# UPCNSL-ABS-FLS-ARD.net
KiCad netlist of a schematic drawn in Altium Designer
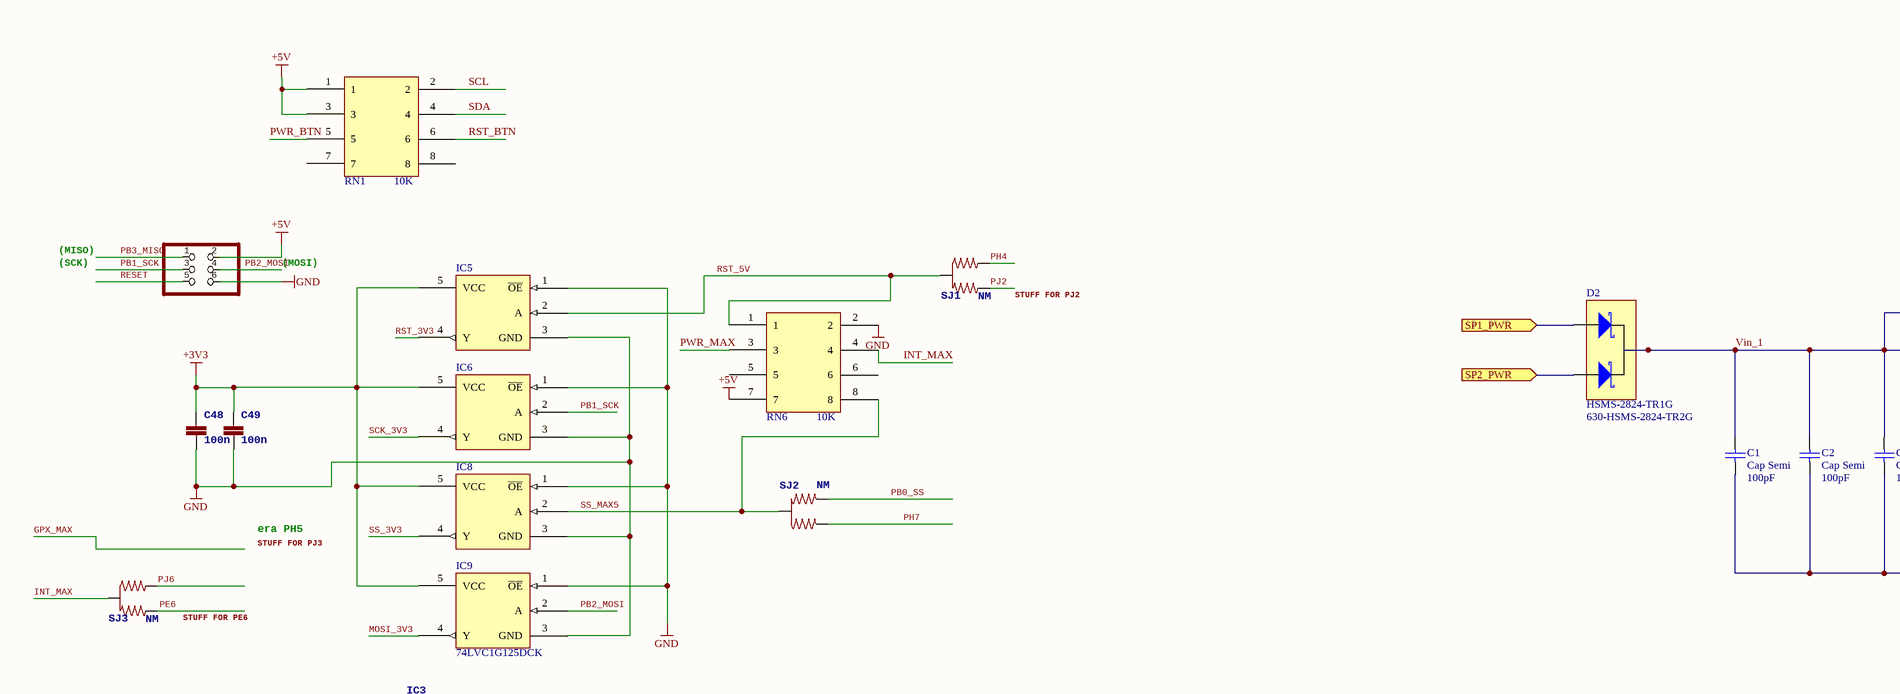
[diagram p0: UPCNSL-ABS-FLS-ARD.SchDoc, top left]
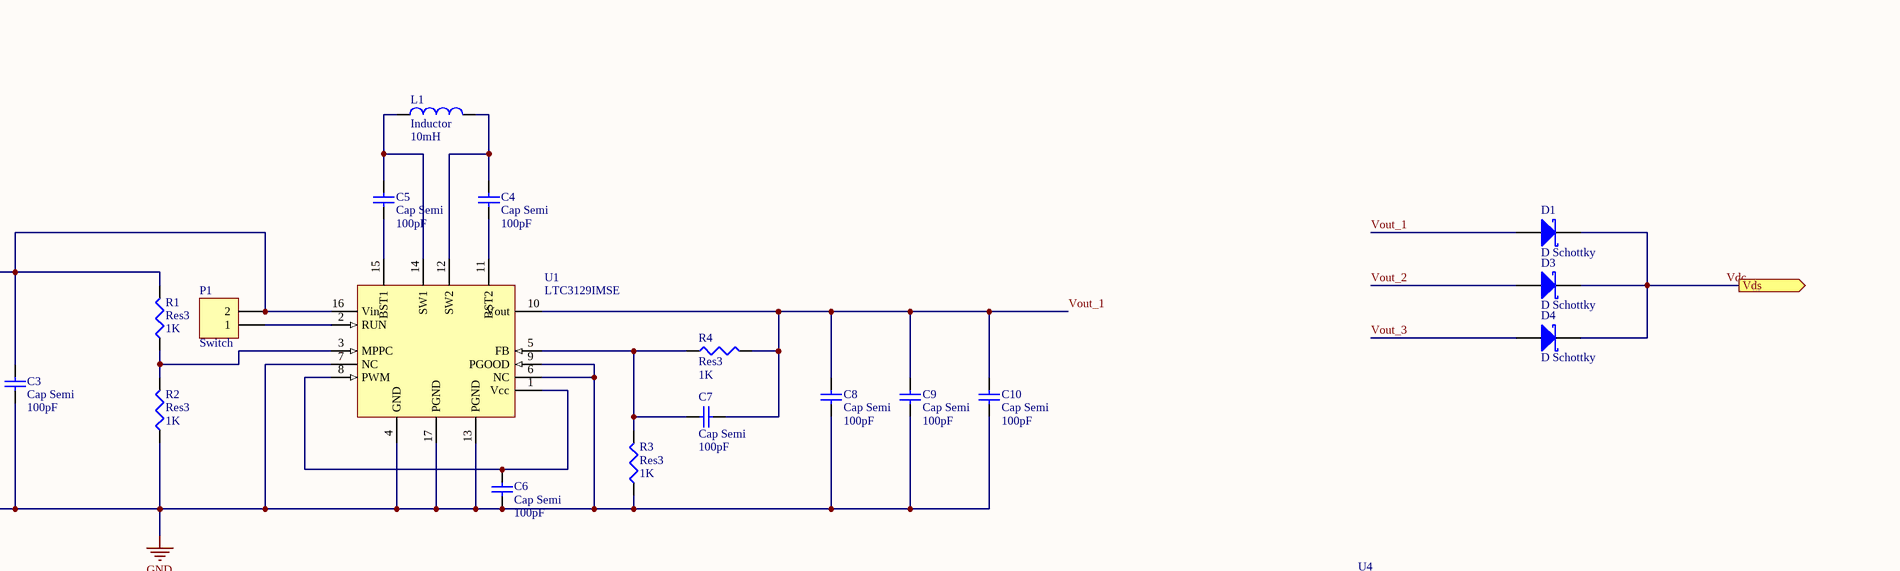
[diagram p1: UPCNSL-ABS-FLS-ARD.SchDoc, top right]
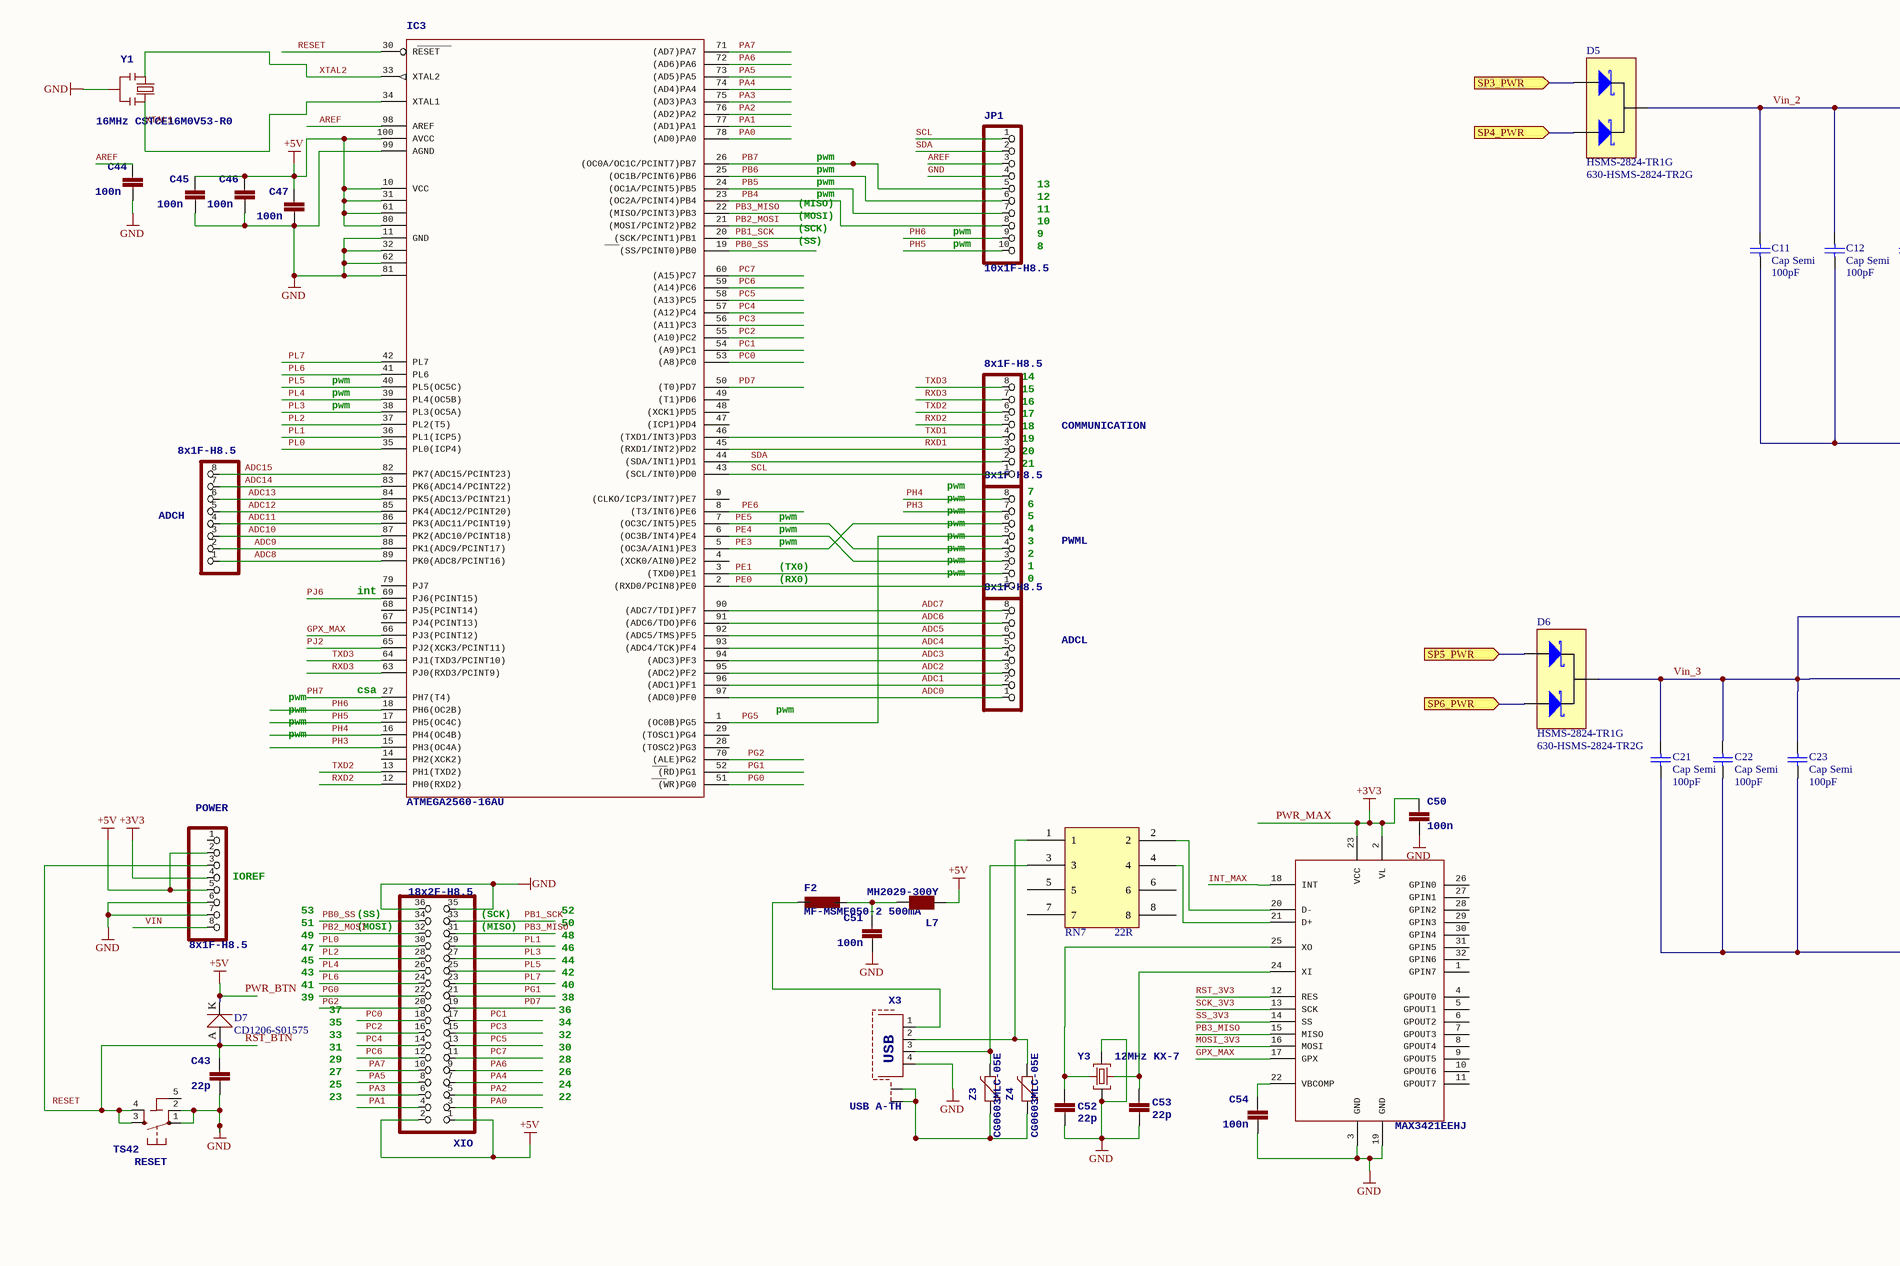
[diagram p2: UPCNSL-ABS-FLS-ARD.SchDoc, bottom left]
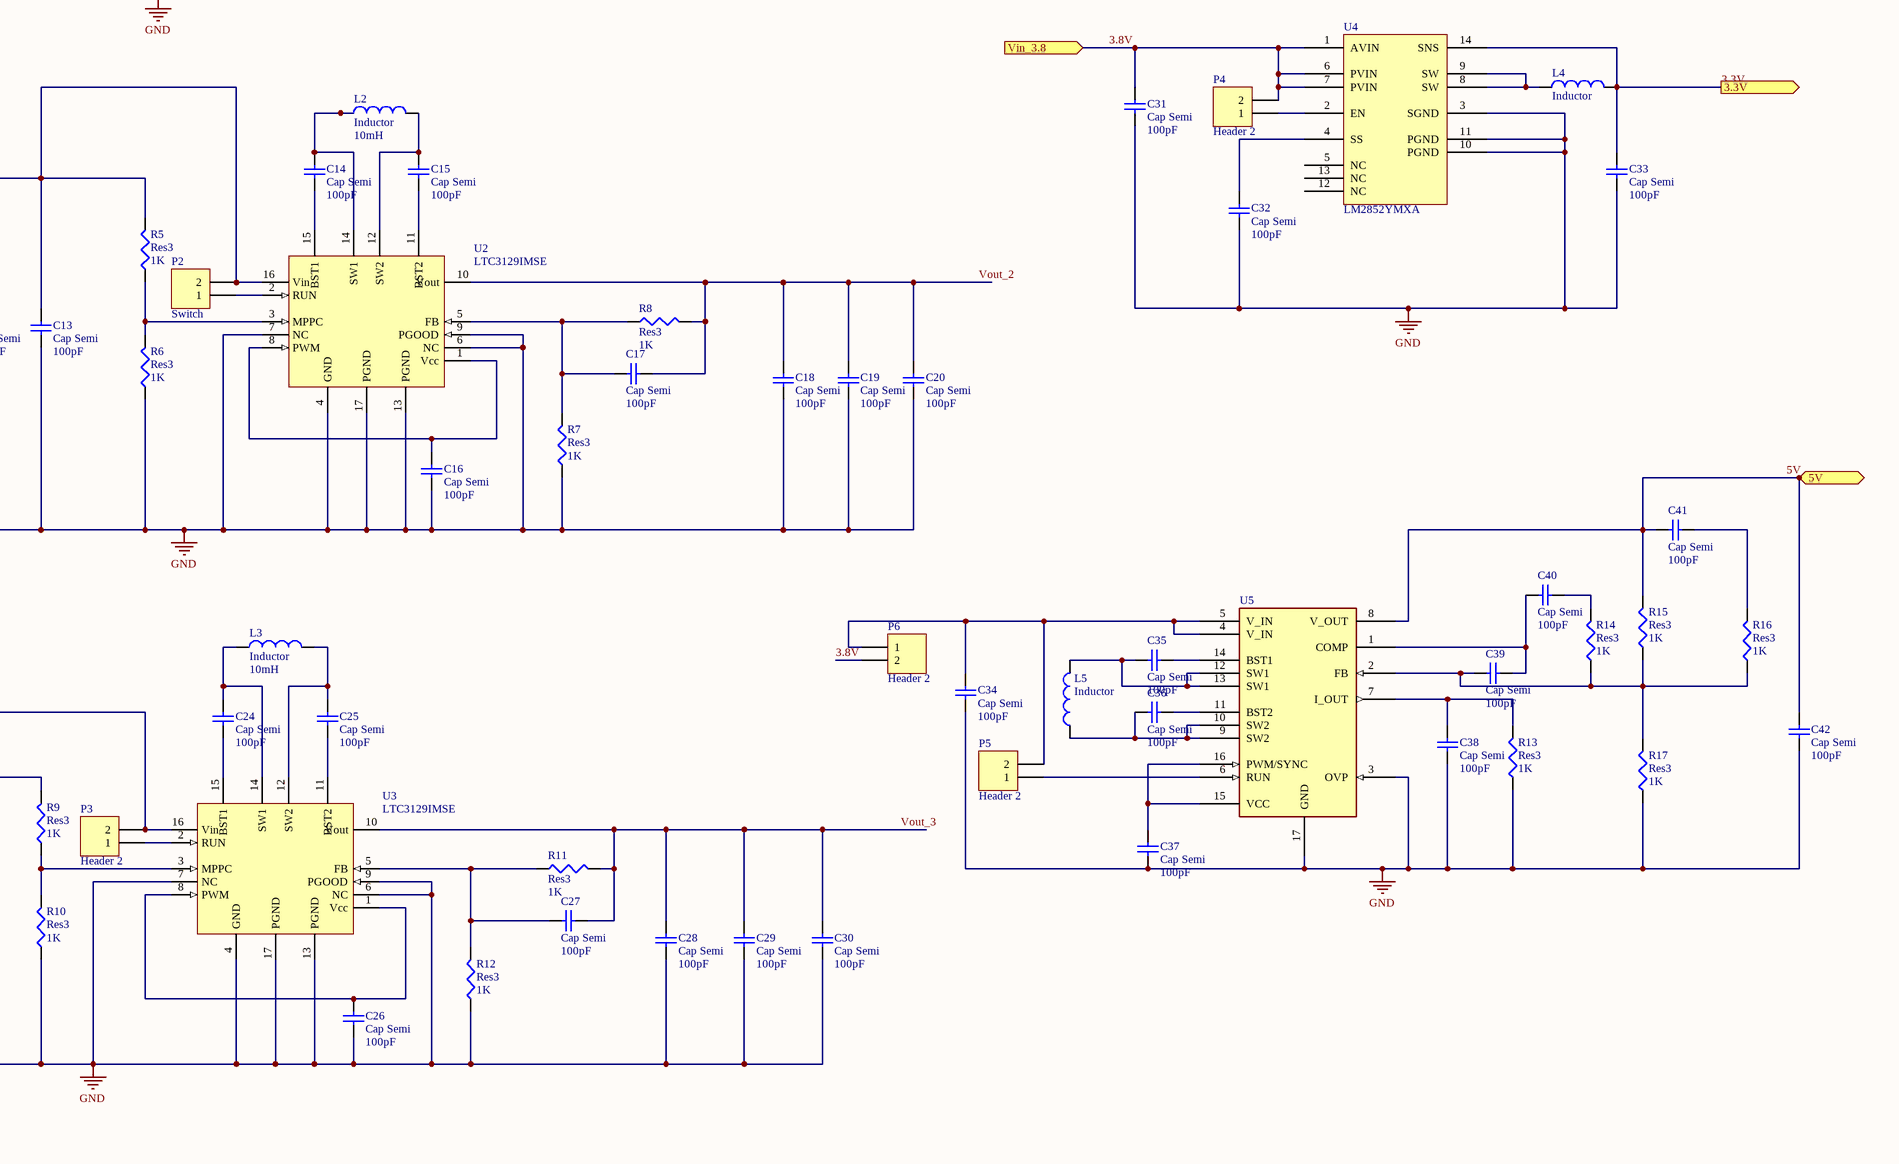
[diagram p3: UPCNSL-ABS-FLS-ARD.SchDoc, bottom right]

(export (version "E")
  (design (tool "Eeschema 10.0.6"))
  (components
    (comp (ref "ADCH")
      (value "8x1F-H8.5")
      (footprint "ADCH")
      (description "<b>PIN HEADER</b>")
      (libsource (lib "SmartPrj") (part "PINHD-1X8"))
    )
    (comp (ref "ADCL")
      (value "8x1F-H8.5")
      (footprint "ADCL")
      (description "<b>PIN HEADER</b>")
      (libsource (lib "SmartPrj") (part "PINHD-1X8"))
    )
    (comp (ref "C1")
      (value "Cap Semi")
      (footprint "1608[0603]")
      (description "Capacitor (Semiconductor SIM Model)")
      (fields (field (name "ALTIUM_VALUE") "100pF") (field (name "PUBLISHER") "Altium Limited"))
      (libsource (lib "Miscellaneous Devices") (part "Cap Semi"))
    )
    (comp (ref "C2")
      (value "Cap Semi")
      (footprint "1608[0603]")
      (description "Capacitor (Semiconductor SIM Model)")
      (fields (field (name "ALTIUM_VALUE") "100pF") (field (name "PUBLISHER") "Altium Limited"))
      (libsource (lib "Miscellaneous Devices") (part "Cap Semi"))
    )
    (comp (ref "C3")
      (value "Cap Semi")
      (footprint "1608[0603]")
      (description "Capacitor (Semiconductor SIM Model)")
      (fields (field (name "ALTIUM_VALUE") "100pF") (field (name "PUBLISHER") "Altium Limited"))
      (libsource (lib "Miscellaneous Devices") (part "Cap Semi"))
    )
    (comp (ref "C4")
      (value "Cap Semi")
      (footprint "1608[0603]")
      (description "Capacitor (Semiconductor SIM Model)")
      (fields (field (name "ALTIUM_VALUE") "100pF") (field (name "PUBLISHER") "Altium Limited"))
      (libsource (lib "Miscellaneous Devices") (part "Cap Semi"))
    )
    (comp (ref "C5")
      (value "Cap Semi")
      (footprint "1608[0603]")
      (description "Capacitor (Semiconductor SIM Model)")
      (fields (field (name "ALTIUM_VALUE") "100pF") (field (name "PUBLISHER") "Altium Limited"))
      (libsource (lib "Miscellaneous Devices") (part "Cap Semi"))
    )
    (comp (ref "C6")
      (value "Cap Semi")
      (footprint "1608[0603]")
      (description "Capacitor (Semiconductor SIM Model)")
      (fields (field (name "ALTIUM_VALUE") "100pF") (field (name "PUBLISHER") "Altium Limited"))
      (libsource (lib "Miscellaneous Devices") (part "Cap Semi"))
    )
    (comp (ref "C7")
      (value "Cap Semi")
      (footprint "1608[0603]")
      (description "Capacitor (Semiconductor SIM Model)")
      (fields (field (name "ALTIUM_VALUE") "100pF") (field (name "PUBLISHER") "Altium Limited"))
      (libsource (lib "Miscellaneous Devices") (part "Cap Semi"))
    )
    (comp (ref "C8")
      (value "Cap Semi")
      (footprint "1608[0603]")
      (description "Capacitor (Semiconductor SIM Model)")
      (fields (field (name "ALTIUM_VALUE") "100pF") (field (name "PUBLISHER") "Altium Limited"))
      (libsource (lib "Miscellaneous Devices") (part "Cap Semi"))
    )
    (comp (ref "C9")
      (value "Cap Semi")
      (footprint "1608[0603]")
      (description "Capacitor (Semiconductor SIM Model)")
      (fields (field (name "ALTIUM_VALUE") "100pF") (field (name "PUBLISHER") "Altium Limited"))
      (libsource (lib "Miscellaneous Devices") (part "Cap Semi"))
    )
    (comp (ref "C10")
      (value "Cap Semi")
      (footprint "1608[0603]")
      (description "Capacitor (Semiconductor SIM Model)")
      (fields (field (name "ALTIUM_VALUE") "100pF") (field (name "PUBLISHER") "Altium Limited"))
      (libsource (lib "Miscellaneous Devices") (part "Cap Semi"))
    )
    (comp (ref "C11")
      (value "Cap Semi")
      (footprint "1608[0603]")
      (description "Capacitor (Semiconductor SIM Model)")
      (fields (field (name "ALTIUM_VALUE") "100pF") (field (name "PUBLISHER") "Altium Limited"))
      (libsource (lib "Miscellaneous Devices") (part "Cap Semi"))
    )
    (comp (ref "C12")
      (value "Cap Semi")
      (footprint "1608[0603]")
      (description "Capacitor (Semiconductor SIM Model)")
      (fields (field (name "ALTIUM_VALUE") "100pF") (field (name "PUBLISHER") "Altium Limited"))
      (libsource (lib "Miscellaneous Devices") (part "Cap Semi"))
    )
    (comp (ref "C13")
      (value "Cap Semi")
      (footprint "1608[0603]")
      (description "Capacitor (Semiconductor SIM Model)")
      (fields (field (name "ALTIUM_VALUE") "100pF") (field (name "PUBLISHER") "Altium Limited"))
      (libsource (lib "Miscellaneous Devices") (part "Cap Semi"))
    )
    (comp (ref "C14")
      (value "Cap Semi")
      (footprint "1608[0603]")
      (description "Capacitor (Semiconductor SIM Model)")
      (fields (field (name "ALTIUM_VALUE") "100pF") (field (name "PUBLISHER") "Altium Limited"))
      (libsource (lib "Miscellaneous Devices") (part "Cap Semi"))
    )
    (comp (ref "C15")
      (value "Cap Semi")
      (footprint "1608[0603]")
      (description "Capacitor (Semiconductor SIM Model)")
      (fields (field (name "ALTIUM_VALUE") "100pF") (field (name "PUBLISHER") "Altium Limited"))
      (libsource (lib "Miscellaneous Devices") (part "Cap Semi"))
    )
    (comp (ref "C16")
      (value "Cap Semi")
      (footprint "1608[0603]")
      (description "Capacitor (Semiconductor SIM Model)")
      (fields (field (name "ALTIUM_VALUE") "100pF") (field (name "PUBLISHER") "Altium Limited"))
      (libsource (lib "Miscellaneous Devices") (part "Cap Semi"))
    )
    (comp (ref "C17")
      (value "Cap Semi")
      (footprint "1608[0603]")
      (description "Capacitor (Semiconductor SIM Model)")
      (fields (field (name "ALTIUM_VALUE") "100pF") (field (name "PUBLISHER") "Altium Limited"))
      (libsource (lib "Miscellaneous Devices") (part "Cap Semi"))
    )
    (comp (ref "C18")
      (value "Cap Semi")
      (footprint "1608[0603]")
      (description "Capacitor (Semiconductor SIM Model)")
      (fields (field (name "ALTIUM_VALUE") "100pF") (field (name "PUBLISHER") "Altium Limited"))
      (libsource (lib "Miscellaneous Devices") (part "Cap Semi"))
    )
    (comp (ref "C19")
      (value "Cap Semi")
      (footprint "1608[0603]")
      (description "Capacitor (Semiconductor SIM Model)")
      (fields (field (name "ALTIUM_VALUE") "100pF") (field (name "PUBLISHER") "Altium Limited"))
      (libsource (lib "Miscellaneous Devices") (part "Cap Semi"))
    )
    (comp (ref "C20")
      (value "Cap Semi")
      (footprint "1608[0603]")
      (description "Capacitor (Semiconductor SIM Model)")
      (fields (field (name "ALTIUM_VALUE") "100pF") (field (name "PUBLISHER") "Altium Limited"))
      (libsource (lib "Miscellaneous Devices") (part "Cap Semi"))
    )
    (comp (ref "C21")
      (value "Cap Semi")
      (footprint "1608[0603]")
      (description "Capacitor (Semiconductor SIM Model)")
      (fields (field (name "ALTIUM_VALUE") "100pF") (field (name "PUBLISHER") "Altium Limited"))
      (libsource (lib "Miscellaneous Devices") (part "Cap Semi"))
    )
    (comp (ref "C22")
      (value "Cap Semi")
      (footprint "1608[0603]")
      (description "Capacitor (Semiconductor SIM Model)")
      (fields (field (name "ALTIUM_VALUE") "100pF") (field (name "PUBLISHER") "Altium Limited"))
      (libsource (lib "Miscellaneous Devices") (part "Cap Semi"))
    )
    (comp (ref "C23")
      (value "Cap Semi")
      (footprint "1608[0603]")
      (description "Capacitor (Semiconductor SIM Model)")
      (fields (field (name "ALTIUM_VALUE") "100pF") (field (name "PUBLISHER") "Altium Limited"))
      (libsource (lib "Miscellaneous Devices") (part "Cap Semi"))
    )
    (comp (ref "C24")
      (value "Cap Semi")
      (footprint "1608[0603]")
      (description "Capacitor (Semiconductor SIM Model)")
      (fields (field (name "ALTIUM_VALUE") "100pF") (field (name "PUBLISHER") "Altium Limited"))
      (libsource (lib "Miscellaneous Devices") (part "Cap Semi"))
    )
    (comp (ref "C25")
      (value "Cap Semi")
      (footprint "1608[0603]")
      (description "Capacitor (Semiconductor SIM Model)")
      (fields (field (name "ALTIUM_VALUE") "100pF") (field (name "PUBLISHER") "Altium Limited"))
      (libsource (lib "Miscellaneous Devices") (part "Cap Semi"))
    )
    (comp (ref "C26")
      (value "Cap Semi")
      (footprint "1608[0603]")
      (description "Capacitor (Semiconductor SIM Model)")
      (fields (field (name "ALTIUM_VALUE") "100pF") (field (name "PUBLISHER") "Altium Limited"))
      (libsource (lib "Miscellaneous Devices") (part "Cap Semi"))
    )
    (comp (ref "C27")
      (value "Cap Semi")
      (footprint "1608[0603]")
      (description "Capacitor (Semiconductor SIM Model)")
      (fields (field (name "ALTIUM_VALUE") "100pF") (field (name "PUBLISHER") "Altium Limited"))
      (libsource (lib "Miscellaneous Devices") (part "Cap Semi"))
    )
    (comp (ref "C28")
      (value "Cap Semi")
      (footprint "1608[0603]")
      (description "Capacitor (Semiconductor SIM Model)")
      (fields (field (name "ALTIUM_VALUE") "100pF") (field (name "PUBLISHER") "Altium Limited"))
      (libsource (lib "Miscellaneous Devices") (part "Cap Semi"))
    )
    (comp (ref "C29")
      (value "Cap Semi")
      (footprint "1608[0603]")
      (description "Capacitor (Semiconductor SIM Model)")
      (fields (field (name "ALTIUM_VALUE") "100pF") (field (name "PUBLISHER") "Altium Limited"))
      (libsource (lib "Miscellaneous Devices") (part "Cap Semi"))
    )
    (comp (ref "C30")
      (value "Cap Semi")
      (footprint "1608[0603]")
      (description "Capacitor (Semiconductor SIM Model)")
      (fields (field (name "ALTIUM_VALUE") "100pF") (field (name "PUBLISHER") "Altium Limited"))
      (libsource (lib "Miscellaneous Devices") (part "Cap Semi"))
    )
    (comp (ref "C31")
      (value "Cap Semi")
      (footprint "1608[0603]")
      (description "Capacitor (Semiconductor SIM Model)")
      (fields (field (name "ALTIUM_VALUE") "100pF") (field (name "PUBLISHER") "Altium Limited"))
      (libsource (lib "Miscellaneous Devices") (part "Cap Semi"))
    )
    (comp (ref "C32")
      (value "Cap Semi")
      (footprint "1608[0603]")
      (description "Capacitor (Semiconductor SIM Model)")
      (fields (field (name "ALTIUM_VALUE") "100pF") (field (name "PUBLISHER") "Altium Limited"))
      (libsource (lib "Miscellaneous Devices") (part "Cap Semi"))
    )
    (comp (ref "C33")
      (value "Cap Semi")
      (footprint "1608[0603]")
      (description "Capacitor (Semiconductor SIM Model)")
      (fields (field (name "ALTIUM_VALUE") "100pF") (field (name "PUBLISHER") "Altium Limited"))
      (libsource (lib "Miscellaneous Devices") (part "Cap Semi"))
    )
    (comp (ref "C34")
      (value "Cap Semi")
      (footprint "1608[0603]")
      (description "Capacitor (Semiconductor SIM Model)")
      (fields (field (name "ALTIUM_VALUE") "100pF") (field (name "PUBLISHER") "Altium Limited"))
      (libsource (lib "Miscellaneous Devices") (part "Cap Semi"))
    )
    (comp (ref "C35")
      (value "Cap Semi")
      (footprint "1608[0603]")
      (description "Capacitor (Semiconductor SIM Model)")
      (fields (field (name "ALTIUM_VALUE") "100pF") (field (name "PUBLISHER") "Altium Limited"))
      (libsource (lib "Miscellaneous Devices") (part "Cap Semi"))
    )
    (comp (ref "C36")
      (value "Cap Semi")
      (footprint "1608[0603]")
      (description "Capacitor (Semiconductor SIM Model)")
      (fields (field (name "ALTIUM_VALUE") "100pF") (field (name "PUBLISHER") "Altium Limited"))
      (libsource (lib "Miscellaneous Devices") (part "Cap Semi"))
    )
    (comp (ref "C37")
      (value "Cap Semi")
      (footprint "1608[0603]")
      (description "Capacitor (Semiconductor SIM Model)")
      (fields (field (name "ALTIUM_VALUE") "100pF") (field (name "PUBLISHER") "Altium Limited"))
      (libsource (lib "Miscellaneous Devices") (part "Cap Semi"))
    )
    (comp (ref "C38")
      (value "Cap Semi")
      (footprint "1608[0603]")
      (description "Capacitor (Semiconductor SIM Model)")
      (fields (field (name "ALTIUM_VALUE") "100pF") (field (name "PUBLISHER") "Altium Limited"))
      (libsource (lib "Miscellaneous Devices") (part "Cap Semi"))
    )
    (comp (ref "C39")
      (value "Cap Semi")
      (footprint "1608[0603]")
      (description "Capacitor (Semiconductor SIM Model)")
      (fields (field (name "ALTIUM_VALUE") "100pF") (field (name "PUBLISHER") "Altium Limited"))
      (libsource (lib "Miscellaneous Devices") (part "Cap Semi"))
    )
    (comp (ref "C40")
      (value "Cap Semi")
      (footprint "1608[0603]")
      (description "Capacitor (Semiconductor SIM Model)")
      (fields (field (name "ALTIUM_VALUE") "100pF") (field (name "PUBLISHER") "Altium Limited"))
      (libsource (lib "Miscellaneous Devices") (part "Cap Semi"))
    )
    (comp (ref "C41")
      (value "Cap Semi")
      (footprint "1608[0603]")
      (description "Capacitor (Semiconductor SIM Model)")
      (fields (field (name "ALTIUM_VALUE") "100pF") (field (name "PUBLISHER") "Altium Limited"))
      (libsource (lib "Miscellaneous Devices") (part "Cap Semi"))
    )
    (comp (ref "C42")
      (value "Cap Semi")
      (footprint "1608[0603]")
      (description "Capacitor (Semiconductor SIM Model)")
      (fields (field (name "ALTIUM_VALUE") "100pF") (field (name "PUBLISHER") "Altium Limited"))
      (libsource (lib "Miscellaneous Devices") (part "Cap Semi"))
    )
    (comp (ref "C43")
      (value "22p")
      (footprint "CAP0603")
      (description "<B>CAPACITOR</B>, European symbol")
      (fields (field (name ">NAME") "C43") (field (name ">VALUE") "22p"))
      (libsource (lib "SmartPrj") (part "C-EU0603-RND"))
    )
    (comp (ref "C44")
      (value "100n")
      (footprint "CAP0603")
      (description "<B>CAPACITOR</B>, European symbol")
      (libsource (lib "SmartPrj") (part "C-EU0603-RND"))
    )
    (comp (ref "C45")
      (value "100n")
      (footprint "CAP0603")
      (description "<B>CAPACITOR</B>, European symbol")
      (libsource (lib "SmartPrj") (part "C-EU0603-RND"))
    )
    (comp (ref "C46")
      (value "100n")
      (footprint "CAP0603")
      (description "<B>CAPACITOR</B>, European symbol")
      (libsource (lib "SmartPrj") (part "C-EU0603-RND"))
    )
    (comp (ref "C47")
      (value "100n")
      (footprint "CAP0603")
      (description "<B>CAPACITOR</B>, European symbol")
      (libsource (lib "SmartPrj") (part "C-EU0603-RND"))
    )
    (comp (ref "C48")
      (value "100n")
      (footprint "CAP0603")
      (description "<B>CAPACITOR</B>, European symbol")
      (fields (field (name ">NAME") "C48") (field (name ">VALUE") "100n"))
      (libsource (lib "") (part "C-EU0603-RND_2"))
    )
    (comp (ref "C49")
      (value "100n")
      (footprint "CAP0603")
      (description "<B>CAPACITOR</B>, European symbol")
      (fields (field (name ">NAME") "C49") (field (name ">VALUE") "100n"))
      (libsource (lib "") (part "C-EU0603-RND_2"))
    )
    (comp (ref "C50")
      (value "100n")
      (footprint "CAP0603")
      (description "<B>CAPACITOR</B>, European symbol")
      (fields (field (name ">NAME") "C50") (field (name ">VALUE") "100n"))
      (libsource (lib "") (part "C-EU0603-RND_2"))
    )
    (comp (ref "C51")
      (value "100n")
      (footprint "CAP0603")
      (description "<B>CAPACITOR</B>, European symbol")
      (fields (field (name ">NAME") "C51") (field (name ">VALUE") "100n"))
      (libsource (lib "SmartPrj") (part "C-EU0603-RND"))
    )
    (comp (ref "C52")
      (value "22p")
      (footprint "CAP0603")
      (description "<B>CAPACITOR</B>, European symbol")
      (libsource (lib "") (part "C-EU0603-RND_1"))
    )
    (comp (ref "C53")
      (value "22p")
      (footprint "CAP0603")
      (description "<B>CAPACITOR</B>, European symbol")
      (libsource (lib "") (part "C-EU0603-RND_1"))
    )
    (comp (ref "C54")
      (value "100n")
      (footprint "CAP0603")
      (description "<B>CAPACITOR</B>, European symbol")
      (fields (field (name ">NAME") "C54") (field (name ">VALUE") "100n"))
      (libsource (lib "SmartPrj") (part "C-EU0603-RND"))
    )
    (comp (ref "COMMUNICATION")
      (value "8x1F-H8.5")
      (footprint "COMMUNICATION")
      (description "<b>PIN HEADER</b>")
      (libsource (lib "SmartPrj") (part "PINHD-1X8"))
    )
    (comp (ref "D1")
      (value "D Schottky")
      (footprint "SMB")
      (description "Schottky Diode")
      (fields (field (name "PUBLISHER") "Altium Limited"))
      (libsource (lib "Miscellaneous Devices") (part "D Schottky"))
    )
    (comp (ref "D2")
      (value "HSMS-2824-TR1G")
      (footprint "SOT23-3")
      (description "DIODE, RF, SCHOTTKY, DUAL, SOT-23")
      (fields (field (name "SUPPLIER PART NUMBER 1") "630-HSMS-2824-TR2G"))
      (libsource (lib "Arduino_Space") (part "HSMS-2824-TR1G"))
    )
    (comp (ref "D3")
      (value "D Schottky")
      (footprint "SMB")
      (description "Schottky Diode")
      (fields (field (name "PUBLISHER") "Altium Limited"))
      (libsource (lib "Miscellaneous Devices") (part "D Schottky"))
    )
    (comp (ref "D4")
      (value "D Schottky")
      (footprint "SMB")
      (description "Schottky Diode")
      (fields (field (name "PUBLISHER") "Altium Limited"))
      (libsource (lib "Miscellaneous Devices") (part "D Schottky"))
    )
    (comp (ref "D5")
      (value "HSMS-2824-TR1G")
      (footprint "SOT23-3")
      (description "DIODE, RF, SCHOTTKY, DUAL, SOT-23")
      (fields (field (name "SUPPLIER PART NUMBER 1") "630-HSMS-2824-TR2G"))
      (libsource (lib "Arduino_Space") (part "HSMS-2824-TR1G"))
    )
    (comp (ref "D6")
      (value "HSMS-2824-TR1G")
      (footprint "SOT23-3")
      (description "DIODE, RF, SCHOTTKY, DUAL, SOT-23")
      (fields (field (name "SUPPLIER PART NUMBER 1") "630-HSMS-2824-TR2G"))
      (libsource (lib "Arduino_Space") (part "HSMS-2824-TR1G"))
    )
    (comp (ref "D7")
      (value "CD1206-S01575")
      (footprint "SMD DIODE")
      (libsource (lib "Arduino_Space") (part "DIODE"))
    )
    (comp (ref "F2")
      (value "MF-MSMF050-2 500mA")
      (footprint "FUSE")
      (description "<B>INDUCTOR</B>, European symbol")
      (fields (field (name ">NAME") "F2") (field (name ">VALUE") "MF-MSMF050-2 500mA"))
      (libsource (lib "rcl") (part "L-EUL1812"))
    )
    (comp (ref "IC3")
      (value "ATMEGA2560-16AU")
      (footprint "TSQFP50P1600X1600X120-100N")
      (libsource (lib "SmartPrj") (part "ATMEGA2560AU"))
    )
    (comp (ref "IC5")
      (value "74LVC1G125DCK")
      (footprint "SOT65P210X110-5N")
      (libsource (lib "Arduino_Space") (part "74LVC1G125DCK"))
    )
    (comp (ref "IC6")
      (value "74LVC1G125DCK")
      (footprint "SOT65P210X110-5N")
      (libsource (lib "Arduino_Space") (part "74LVC1G125DCK"))
    )
    (comp (ref "IC8")
      (value "74LVC1G125DCK")
      (footprint "SOT65P210X110-5N")
      (libsource (lib "Arduino_Space") (part "74LVC1G125DCK"))
    )
    (comp (ref "IC9")
      (value "74LVC1G125DCK")
      (footprint "SOT65P210X110-5N")
      (libsource (lib "Arduino_Space") (part "74LVC1G125DCK"))
    )
    (comp (ref "ICSP")
      (value "3x2M")
      (footprint "Header 3x2")
      (description "<b>PIN HEADER</b>")
      (libsource (lib "SmartPrj") (part "PINHD-2X3"))
    )
    (comp (ref "JP1")
      (value "10x1F-H8.5")
      (footprint "HEADER 1X10")
      (description "<b>PIN HEADER</b>")
      (fields (field (name ">NAME") "JP1") (field (name ">VALUE") "10x1F-H8.5"))
      (libsource (lib "SmartPrj") (part "PINHD-1X10"))
    )
    (comp (ref "L1")
      (value "Inductor")
      (footprint "0603")
      (fields (field (name "ALTIUM_VALUE") "10mH") (field (name "PUBLISHER") "Altium Limited"))
      (libsource (lib "Miscellaneous Devices") (part "Inductor"))
    )
    (comp (ref "L2")
      (value "Inductor")
      (footprint "0603")
      (fields (field (name "ALTIUM_VALUE") "10mH") (field (name "PUBLISHER") "Altium Limited"))
      (libsource (lib "Miscellaneous Devices") (part "Inductor"))
    )
    (comp (ref "L3")
      (value "Inductor")
      (footprint "0603")
      (fields (field (name "ALTIUM_VALUE") "10mH") (field (name "PUBLISHER") "Altium Limited"))
      (libsource (lib "Miscellaneous Devices") (part "Inductor"))
    )
    (comp (ref "L4")
      (value "Inductor")
      (footprint "0402-A")
      (fields (field (name "PUBLISHER") "Altium Limited"))
      (libsource (lib "Miscellaneous Devices") (part "Inductor"))
    )
    (comp (ref "L5")
      (value "Inductor")
      (footprint "0402-A")
      (fields (field (name "PUBLISHER") "Altium Limited"))
      (libsource (lib "Miscellaneous Devices") (part "Inductor"))
    )
    (comp (ref "L7")
      (value "MH2029-300Y")
      (footprint "INDUCTOR")
      (fields (field (name ">VALUE") "MH2029-300Y") (field (name ">NAME") "L7"))
      (libsource (lib "wuerth-elektronik") (part "WE-CBF_0805"))
    )
    (comp (ref "P1")
      (value "Switch")
      (footprint "HDR1X2")
      (description "Header, 2-Pin")
      (fields (field (name "PUBLISHER") "Altium Limited"))
      (libsource (lib "") (part "Header 2_1"))
    )
    (comp (ref "P2")
      (value "Switch")
      (footprint "HDR1X2")
      (description "Header, 2-Pin")
      (fields (field (name "PUBLISHER") "Altium Limited"))
      (libsource (lib "") (part "Header 2_1"))
    )
    (comp (ref "P3")
      (value "Header 2")
      (footprint "HDR1X2")
      (description "Header, 2-Pin")
      (fields (field (name "PUBLISHER") "Altium Limited"))
      (libsource (lib "") (part "Header 2_1"))
    )
    (comp (ref "P4")
      (value "Header 2")
      (footprint "HDR1X2")
      (description "Header, 2-Pin")
      (fields (field (name "PUBLISHER") "Altium Limited"))
      (libsource (lib "") (part "Header 2_1"))
    )
    (comp (ref "P5")
      (value "Header 2")
      (footprint "HDR1X2")
      (description "Header, 2-Pin")
      (fields (field (name "PUBLISHER") "Altium Limited"))
      (libsource (lib "") (part "Header 2_1"))
    )
    (comp (ref "P6")
      (value "Header 2")
      (footprint "HDR1X2")
      (description "Header, 2-Pin")
      (fields (field (name "PUBLISHER") "Altium Limited"))
      (libsource (lib "Miscellaneous Connectors") (part "Header 2"))
    )
    (comp (ref "POWER")
      (value "8x1F-H8.5")
      (footprint "POWER")
      (description "<b>PIN HEADER</b>")
      (libsource (lib "SmartPrj") (part "PINHD-1X8"))
    )
    (comp (ref "PWML")
      (value "8x1F-H8.5")
      (footprint "PWM")
      (description "<b>PIN HEADER</b>")
      (libsource (lib "SmartPrj") (part "PINHD-1X8"))
    )
    (comp (ref "R1")
      (value "Res3")
      (footprint "J1-0603")
      (description "Resistor")
      (fields (field (name "ALTIUM_VALUE") "1K") (field (name "PUBLISHER") "Altium Limited"))
      (libsource (lib "Miscellaneous Devices") (part "Res3"))
    )
    (comp (ref "R2")
      (value "Res3")
      (footprint "J1-0603")
      (description "Resistor")
      (fields (field (name "ALTIUM_VALUE") "1K") (field (name "PUBLISHER") "Altium Limited"))
      (libsource (lib "Miscellaneous Devices") (part "Res3"))
    )
    (comp (ref "R3")
      (value "Res3")
      (footprint "J1-0603")
      (description "Resistor")
      (fields (field (name "ALTIUM_VALUE") "1K") (field (name "PUBLISHER") "Altium Limited"))
      (libsource (lib "Miscellaneous Devices") (part "Res3"))
    )
    (comp (ref "R4")
      (value "Res3")
      (footprint "J1-0603")
      (description "Resistor")
      (fields (field (name "ALTIUM_VALUE") "1K") (field (name "PUBLISHER") "Altium Limited"))
      (libsource (lib "Miscellaneous Devices") (part "Res3"))
    )
    (comp (ref "R5")
      (value "Res3")
      (footprint "J1-0603")
      (description "Resistor")
      (fields (field (name "ALTIUM_VALUE") "1K") (field (name "PUBLISHER") "Altium Limited"))
      (libsource (lib "Miscellaneous Devices") (part "Res3"))
    )
    (comp (ref "R6")
      (value "Res3")
      (footprint "J1-0603")
      (description "Resistor")
      (fields (field (name "ALTIUM_VALUE") "1K") (field (name "PUBLISHER") "Altium Limited"))
      (libsource (lib "Miscellaneous Devices") (part "Res3"))
    )
    (comp (ref "R7")
      (value "Res3")
      (footprint "J1-0603")
      (description "Resistor")
      (fields (field (name "ALTIUM_VALUE") "1K") (field (name "PUBLISHER") "Altium Limited"))
      (libsource (lib "Miscellaneous Devices") (part "Res3"))
    )
    (comp (ref "R8")
      (value "Res3")
      (footprint "J1-0603")
      (description "Resistor")
      (fields (field (name "ALTIUM_VALUE") "1K") (field (name "PUBLISHER") "Altium Limited"))
      (libsource (lib "Miscellaneous Devices") (part "Res3"))
    )
    (comp (ref "R9")
      (value "Res3")
      (footprint "J1-0603")
      (description "Resistor")
      (fields (field (name "ALTIUM_VALUE") "1K") (field (name "PUBLISHER") "Altium Limited"))
      (libsource (lib "Miscellaneous Devices") (part "Res3"))
    )
    (comp (ref "R10")
      (value "Res3")
      (footprint "J1-0603")
      (description "Resistor")
      (fields (field (name "ALTIUM_VALUE") "1K") (field (name "PUBLISHER") "Altium Limited"))
      (libsource (lib "Miscellaneous Devices") (part "Res3"))
    )
    (comp (ref "R11")
      (value "Res3")
      (footprint "J1-0603")
      (description "Resistor")
      (fields (field (name "ALTIUM_VALUE") "1K") (field (name "PUBLISHER") "Altium Limited"))
      (libsource (lib "Miscellaneous Devices") (part "Res3"))
    )
    (comp (ref "R12")
      (value "Res3")
      (footprint "J1-0603")
      (description "Resistor")
      (fields (field (name "ALTIUM_VALUE") "1K") (field (name "PUBLISHER") "Altium Limited"))
      (libsource (lib "Miscellaneous Devices") (part "Res3"))
    )
    (comp (ref "R13")
      (value "Res3")
      (footprint "J1-0603")
      (description "Resistor")
      (fields (field (name "ALTIUM_VALUE") "1K") (field (name "PUBLISHER") "Altium Limited"))
      (libsource (lib "Miscellaneous Devices") (part "Res3"))
    )
    (comp (ref "R14")
      (value "Res3")
      (footprint "J1-0603")
      (description "Resistor")
      (fields (field (name "ALTIUM_VALUE") "1K") (field (name "PUBLISHER") "Altium Limited"))
      (libsource (lib "Miscellaneous Devices") (part "Res3"))
    )
    (comp (ref "R15")
      (value "Res3")
      (footprint "J1-0603")
      (description "Resistor")
      (fields (field (name "ALTIUM_VALUE") "1K") (field (name "PUBLISHER") "Altium Limited"))
      (libsource (lib "Miscellaneous Devices") (part "Res3"))
    )
    (comp (ref "R16")
      (value "Res3")
      (footprint "J1-0603")
      (description "Resistor")
      (fields (field (name "ALTIUM_VALUE") "1K") (field (name "PUBLISHER") "Altium Limited"))
      (libsource (lib "Miscellaneous Devices") (part "Res3"))
    )
    (comp (ref "R17")
      (value "Res3")
      (footprint "J1-0603")
      (description "Resistor")
      (fields (field (name "ALTIUM_VALUE") "1K") (field (name "PUBLISHER") "Altium Limited"))
      (libsource (lib "Miscellaneous Devices") (part "Res3"))
    )
    (comp (ref "RESET")
      (value "TS42")
      (footprint "TS42")
      (description "TS42\nDongnan Electronics\nTact switch\nVDC 12V - 50mA")
      (fields (field (name ">NAME") "RESET") (field (name ">VALUE") "TS42"))
      (libsource (lib "SmartPrj") (part "TS42"))
    )
    (comp (ref "RN1")
      (value "10K")
      (footprint "CAF-80P319X159-8N")
      (libsource (lib "Arduino_Space") (part "RES_ARRAY"))
    )
    (comp (ref "RN6")
      (value "10K")
      (footprint "CAF-80P319X159-8N")
      (libsource (lib "Arduino_Space") (part "RES_ARRAY"))
    )
    (comp (ref "RN7")
      (value "22R")
      (footprint "CAF-80P319X159-8N")
      (libsource (lib "Arduino_Space") (part "RES_ARRAY"))
    )
    (comp (ref "SJ1")
      (value "NM")
      (footprint "J0402")
      (description "Three terminal jumper made from two 0402, 0603, 0805, etc.")
      (libsource (lib "bibaja") (part "J0402"))
    )
    (comp (ref "SJ2")
      (value "NM")
      (footprint "J0402")
      (description "Three terminal jumper made from two 0402, 0603, 0805, etc.")
      (libsource (lib "bibaja") (part "J0402"))
    )
    (comp (ref "SJ3")
      (value "NM")
      (footprint "J0402")
      (description "Three terminal jumper made from two 0402, 0603, 0805, etc.")
      (libsource (lib "bibaja") (part "J0402"))
    )
    (comp (ref "U1")
      (value "LTC3129IMSE")
      (footprint "MSOP-16")
      (description "15V, 200mA Synchronous Buck-Boost DC/DC Converter with 1.3µA Quiescent Current")
      (libsource (lib "Arduino_Space") (part "LTC3129"))
    )
    (comp (ref "U2")
      (value "LTC3129IMSE")
      (footprint "MSOP-16")
      (description "15V, 200mA Synchronous Buck-Boost DC/DC Converter with 1.3µA Quiescent Current")
      (libsource (lib "Arduino_Space") (part "LTC3129"))
    )
    (comp (ref "U3")
      (value "LTC3129IMSE")
      (footprint "MSOP-16")
      (description "15V, 200mA Synchronous Buck-Boost DC/DC Converter with 1.3µA Quiescent Current")
      (libsource (lib "Arduino_Space") (part "LTC3129"))
    )
    (comp (ref "U4")
      (value "LM2852YMXA")
      (footprint "TSOP65P650X110-14N (LM2852YMXA)")
      (libsource (lib "Arduino_Space") (part "LM2852YMXA"))
    )
    (comp (ref "U5")
      (value "LTC3112EDHD#PBF")
      (footprint "SON50P400X85_HS-17N")
      (description "IC REG BUCK BOOST ADJ 2.5A 16DFN")
      (libsource (lib "Arduino_Space") (part "LTC3112EDHD#PBF"))
    )
    (comp (ref "U7A")
      (value "MAX3421EEHJ")
      (footprint "TSQFP50P700X700X120-32N")
      (description "MAX3421 SPI to USB Interface Chip")
      (libsource (lib "bibaja") (part "MAX3421EEHJ"))
    )
    (comp (ref "X3")
      (value "USB A-TH")
      (footprint "PN87520-S")
      (fields (field (name ">NAME") "X3") (field (name ">VALUE") "USB A-TH") (field (name "USB") "USB"))
      (libsource (lib "SmartPrj") (part "PN87520-S"))
    )
    (comp (ref "XIO")
      (value "18x2F-H8.5")
      (footprint "HEADER 2X18")
      (description "<b>PIN HEADER</b>")
      (fields (field (name ">NAME") "XIO") (field (name ">VALUE") "18x2F-H8.5"))
      (libsource (lib "SmartPrj") (part "PINHD-2X18"))
    )
    (comp (ref "Y1")
      (value "16MHz CSTCE16M0V53-R0")
      (footprint "RESONATOR")
      (libsource (lib "SmartPrj") (part "RESONATORMU"))
    )
    (comp (ref "Y3")
      (value "12MHz KX-7")
      (footprint "CRYSTAL-3.2-2.5")
      (libsource (lib "SmartPrj") (part "CRYSTAL-3.2-2.5"))
    )
    (comp (ref "Z3")
      (value "CG0603MLC-05E")
      (footprint "0603")
      (description "<b>VARISTOR</b>")
      (libsource (lib "varistor") (part "VARISTORCN0603"))
    )
    (comp (ref "Z4")
      (value "CG0603MLC-05E")
      (footprint "0603")
      (description "<b>VARISTOR</b>")
      (libsource (lib "varistor") (part "VARISTORCN0603"))
    )
  )
  (nets
    (net (code "1") (name "+3V3") (class "Default")
      (node (ref "C48") (pin "1") (pinfunction "1_1") (pintype "passive"))
      (node (ref "C49") (pin "1") (pinfunction "1_1") (pintype "passive"))
      (node (ref "C50") (pin "1") (pinfunction "1_1") (pintype "passive"))
      (node (ref "IC5") (pin "5") (pinfunction "VCC_5") (pintype "passive"))
      (node (ref "IC6") (pin "5") (pinfunction "VCC_5") (pintype "passive"))
      (node (ref "IC8") (pin "5") (pinfunction "VCC_5") (pintype "passive"))
      (node (ref "IC9") (pin "5") (pinfunction "VCC_5") (pintype "passive"))
      (node (ref "POWER") (pin "4") (pinfunction "4_4") (pintype "passive"))
      (node (ref "RN6") (pin "3") (pinfunction "3_3") (pintype "passive"))
      (node (ref "U7A") (pin "2") (pinfunction "VL_2") (pintype "passive"))
      (node (ref "U7A") (pin "23") (pinfunction "VCC_23") (pintype "passive"))
    )
    (net (code "2") (name "+5V") (class "Default")
      (node (ref "C45") (pin "1") (pinfunction "1_1") (pintype "passive"))
      (node (ref "C46") (pin "1") (pinfunction "1_1") (pintype "passive"))
      (node (ref "C47") (pin "1") (pinfunction "1_1") (pintype "passive"))
      (node (ref "D7") (pin "K") (pinfunction "K_K") (pintype "passive"))
      (node (ref "IC3") (pin "10") (pinfunction "VCC_10") (pintype "power_in"))
      (node (ref "IC3") (pin "100") (pinfunction "AVCC_100") (pintype "power_in"))
      (node (ref "IC3") (pin "31") (pinfunction "VCC1_31") (pintype "power_in"))
      (node (ref "IC3") (pin "61") (pinfunction "VCC2_61") (pintype "power_in"))
      (node (ref "IC3") (pin "80") (pinfunction "VCC3_80") (pintype "power_in"))
      (node (ref "ICSP") (pin "2") (pinfunction "2_2") (pintype "passive"))
      (node (ref "L7") (pin "1") (pinfunction "1_1") (pintype "passive"))
      (node (ref "POWER") (pin "2") (pinfunction "2_2") (pintype "passive"))
      (node (ref "POWER") (pin "5") (pinfunction "5_5") (pintype "passive"))
      (node (ref "RN1") (pin "1") (pinfunction "1_1") (pintype "passive"))
      (node (ref "RN1") (pin "3") (pinfunction "3_3") (pintype "passive"))
      (node (ref "RN1") (pin "5") (pinfunction "5_5") (pintype "passive"))
      (node (ref "RN6") (pin "7") (pinfunction "7_7") (pintype "passive"))
      (node (ref "XIO") (pin "1") (pinfunction "1_1") (pintype "passive"))
      (node (ref "XIO") (pin "2") (pinfunction "2_2") (pintype "passive"))
    )
    (net (code "3") (name "/3.3V") (class "Default")
      (node (ref "C33") (pin "2") (pinfunction "2_2") (pintype "passive"))
      (node (ref "L4") (pin "2") (pinfunction "2_2") (pintype "passive"))
      (node (ref "U4") (pin "14") (pinfunction "SNS_14") (pintype "passive"))
    )
    (net (code "4") (name "/3.8V") (class "Default")
      (node (ref "C31") (pin "2") (pinfunction "2_2") (pintype "passive"))
      (node (ref "P4") (pin "2") (pinfunction "2_2") (pintype "passive"))
      (node (ref "P6") (pin "2") (pinfunction "2_2") (pintype "passive"))
      (node (ref "U4") (pin "1") (pinfunction "AVIN_1") (pintype "passive"))
      (node (ref "U4") (pin "6") (pinfunction "PVIN_6") (pintype "passive"))
      (node (ref "U4") (pin "7") (pinfunction "PVIN_7") (pintype "passive"))
    )
    (net (code "5") (name "/5V") (class "Default")
      (node (ref "C41") (pin "1") (pinfunction "1_1") (pintype "passive"))
      (node (ref "C42") (pin "2") (pinfunction "2_2") (pintype "passive"))
      (node (ref "R15") (pin "2") (pinfunction "2_2") (pintype "passive"))
      (node (ref "U5") (pin "8") (pinfunction "V_OUT_8") (pintype "passive"))
    )
    (net (code "6") (name "/ADC0") (class "Default")
      (node (ref "ADCL") (pin "1") (pinfunction "1_1") (pintype "passive"))
      (node (ref "IC3") (pin "97") (pinfunction "(ADC0)PF0_97") (pintype "passive"))
    )
    (net (code "7") (name "/ADC1") (class "Default")
      (node (ref "ADCL") (pin "2") (pinfunction "2_2") (pintype "passive"))
      (node (ref "IC3") (pin "96") (pinfunction "(ADC1)PF1_96") (pintype "passive"))
    )
    (net (code "8") (name "/ADC2") (class "Default")
      (node (ref "ADCL") (pin "3") (pinfunction "3_3") (pintype "passive"))
      (node (ref "IC3") (pin "95") (pinfunction "(ADC2)PF2_95") (pintype "passive"))
    )
    (net (code "9") (name "/ADC3") (class "Default")
      (node (ref "ADCL") (pin "4") (pinfunction "4_4") (pintype "passive"))
      (node (ref "IC3") (pin "94") (pinfunction "(ADC3)PF3_94") (pintype "passive"))
    )
    (net (code "10") (name "/ADC4") (class "Default")
      (node (ref "ADCL") (pin "5") (pinfunction "5_5") (pintype "passive"))
      (node (ref "IC3") (pin "93") (pinfunction "(ADC4/TCK)PF4_93") (pintype "passive"))
    )
    (net (code "11") (name "/ADC5") (class "Default")
      (node (ref "ADCL") (pin "6") (pinfunction "6_6") (pintype "passive"))
      (node (ref "IC3") (pin "92") (pinfunction "(ADC5/TMS)PF5_92") (pintype "passive"))
    )
    (net (code "12") (name "/ADC6") (class "Default")
      (node (ref "ADCL") (pin "7") (pinfunction "7_7") (pintype "passive"))
      (node (ref "IC3") (pin "91") (pinfunction "(ADC6/TDO)PF6_91") (pintype "passive"))
    )
    (net (code "13") (name "/ADC7") (class "Default")
      (node (ref "ADCL") (pin "8") (pinfunction "8_8") (pintype "passive"))
      (node (ref "IC3") (pin "90") (pinfunction "(ADC7/TDI)PF7_90") (pintype "passive"))
    )
    (net (code "14") (name "/ADC8") (class "Default")
      (node (ref "ADCH") (pin "1") (pinfunction "1_1") (pintype "passive"))
      (node (ref "IC3") (pin "89") (pinfunction "PK0(ADC8/PCINT16)_89") (pintype "passive"))
    )
    (net (code "15") (name "/ADC9") (class "Default")
      (node (ref "ADCH") (pin "2") (pinfunction "2_2") (pintype "passive"))
      (node (ref "IC3") (pin "88") (pinfunction "PK1(ADC9/PCINT17)_88") (pintype "passive"))
    )
    (net (code "16") (name "/ADC10") (class "Default")
      (node (ref "ADCH") (pin "3") (pinfunction "3_3") (pintype "passive"))
      (node (ref "IC3") (pin "87") (pinfunction "PK2(ADC10/PCINT18)_87") (pintype "passive"))
    )
    (net (code "17") (name "/ADC11") (class "Default")
      (node (ref "ADCH") (pin "4") (pinfunction "4_4") (pintype "passive"))
      (node (ref "IC3") (pin "86") (pinfunction "PK3(ADC11/PCINT19)_86") (pintype "passive"))
    )
    (net (code "18") (name "/ADC12") (class "Default")
      (node (ref "ADCH") (pin "5") (pinfunction "5_5") (pintype "passive"))
      (node (ref "IC3") (pin "85") (pinfunction "PK4(ADC12/PCINT20)_85") (pintype "passive"))
    )
    (net (code "19") (name "/ADC13") (class "Default")
      (node (ref "ADCH") (pin "6") (pinfunction "6_6") (pintype "passive"))
      (node (ref "IC3") (pin "84") (pinfunction "PK5(ADC13/PCINT21)_84") (pintype "passive"))
    )
    (net (code "20") (name "/ADC14") (class "Default")
      (node (ref "ADCH") (pin "7") (pinfunction "7_7") (pintype "passive"))
      (node (ref "IC3") (pin "83") (pinfunction "PK6(ADC14/PCINT22)_83") (pintype "passive"))
    )
    (net (code "21") (name "/ADC15") (class "Default")
      (node (ref "ADCH") (pin "8") (pinfunction "8_8") (pintype "passive"))
      (node (ref "IC3") (pin "82") (pinfunction "PK7(ADC15/PCINT23)_82") (pintype "passive"))
    )
    (net (code "22") (name "/AREF") (class "Default")
      (node (ref "C44") (pin "1") (pinfunction "1_1") (pintype "passive"))
      (node (ref "IC3") (pin "98") (pinfunction "AREF_98") (pintype "passive"))
      (node (ref "JP1") (pin "3") (pinfunction "3_3") (pintype "passive"))
    )
    (net (code "23") (name "/GPX_MAX") (class "Default")
      (node (ref "IC3") (pin "66") (pinfunction "PJ3(PCINT12)_66") (pintype "passive"))
      (node (ref "U7A") (pin "17") (pinfunction "GPX_17") (pintype "passive"))
    )
    (net (code "24") (name "/INT_MAX") (class "Default")
      (node (ref "RN6") (pin "4") (pinfunction "4_4") (pintype "passive"))
      (node (ref "SJ3") (pin "2") (pinfunction "C_2") (pintype "passive"))
      (node (ref "U7A") (pin "18") (pinfunction "INT_18") (pintype "passive"))
    )
    (net (code "25") (name "/MOSI_3V3") (class "Default")
      (node (ref "IC9") (pin "4") (pinfunction "Y_4") (pintype "output"))
      (node (ref "U7A") (pin "16") (pinfunction "MOSI_16") (pintype "passive"))
    )
    (net (code "26") (name "/PA0") (class "Default")
      (node (ref "IC3") (pin "78") (pinfunction "(AD0)PA0_78") (pintype "passive"))
      (node (ref "XIO") (pin "3") (pinfunction "3_3") (pintype "passive"))
    )
    (net (code "27") (name "/PA1") (class "Default")
      (node (ref "IC3") (pin "77") (pinfunction "(AD1)PA1_77") (pintype "passive"))
      (node (ref "XIO") (pin "4") (pinfunction "4_4") (pintype "passive"))
    )
    (net (code "28") (name "/PA2") (class "Default")
      (node (ref "IC3") (pin "76") (pinfunction "(AD2)PA2_76") (pintype "passive"))
      (node (ref "XIO") (pin "5") (pinfunction "5_5") (pintype "passive"))
    )
    (net (code "29") (name "/PA3") (class "Default")
      (node (ref "IC3") (pin "75") (pinfunction "(AD3)PA3_75") (pintype "passive"))
      (node (ref "XIO") (pin "6") (pinfunction "6_6") (pintype "passive"))
    )
    (net (code "30") (name "/PA4") (class "Default")
      (node (ref "IC3") (pin "74") (pinfunction "(AD4)PA4_74") (pintype "passive"))
      (node (ref "XIO") (pin "7") (pinfunction "7_7") (pintype "passive"))
    )
    (net (code "31") (name "/PA5") (class "Default")
      (node (ref "IC3") (pin "73") (pinfunction "(AD5)PA5_73") (pintype "passive"))
      (node (ref "XIO") (pin "8") (pinfunction "8_8") (pintype "passive"))
    )
    (net (code "32") (name "/PA6") (class "Default")
      (node (ref "IC3") (pin "72") (pinfunction "(AD6)PA6_72") (pintype "passive"))
      (node (ref "XIO") (pin "9") (pinfunction "9_9") (pintype "passive"))
    )
    (net (code "33") (name "/PA7") (class "Default")
      (node (ref "IC3") (pin "71") (pinfunction "(AD7)PA7_71") (pintype "passive"))
      (node (ref "XIO") (pin "10") (pinfunction "10_10") (pintype "passive"))
    )
    (net (code "34") (name "/PB0_SS") (class "Default")
      (node (ref "IC3") (pin "19") (pinfunction "(SS/PCINT0)PB0_19") (pintype "passive"))
      (node (ref "SJ2") (pin "3") (pinfunction "2_3") (pintype "passive"))
      (node (ref "XIO") (pin "34") (pinfunction "34_34") (pintype "passive"))
    )
    (net (code "35") (name "/PB1_SCK") (class "Default")
      (node (ref "IC3") (pin "20") (pinfunction "(SCK/PCINT1)PB1_20") (pintype "passive"))
      (node (ref "IC6") (pin "2") (pinfunction "A_2") (pintype "input"))
      (node (ref "ICSP") (pin "3") (pinfunction "3_3") (pintype "passive"))
      (node (ref "XIO") (pin "33") (pinfunction "33_33") (pintype "passive"))
    )
    (net (code "36") (name "/PB2_MOSI") (class "Default")
      (node (ref "IC3") (pin "21") (pinfunction "(MOSI/PCINT2)PB2_21") (pintype "passive"))
      (node (ref "IC9") (pin "2") (pinfunction "A_2") (pintype "input"))
      (node (ref "ICSP") (pin "4") (pinfunction "4_4") (pintype "passive"))
      (node (ref "XIO") (pin "32") (pinfunction "32_32") (pintype "passive"))
    )
    (net (code "37") (name "/PB3_MISO") (class "Default")
      (node (ref "IC3") (pin "22") (pinfunction "(MISO/PCINT3)PB3_22") (pintype "passive"))
      (node (ref "ICSP") (pin "1") (pinfunction "1_1") (pintype "passive"))
      (node (ref "U7A") (pin "15") (pinfunction "MISO_15") (pintype "passive"))
      (node (ref "XIO") (pin "31") (pinfunction "31_31") (pintype "passive"))
    )
    (net (code "38") (name "/PB4") (class "Default")
      (node (ref "IC3") (pin "23") (pinfunction "(OC2A/PCINT4)PB4_23") (pintype "passive"))
      (node (ref "JP1") (pin "8") (pinfunction "8_8") (pintype "passive"))
    )
    (net (code "39") (name "/PB5") (class "Default")
      (node (ref "IC3") (pin "24") (pinfunction "(OC1A/PCINT5)PB5_24") (pintype "passive"))
      (node (ref "JP1") (pin "7") (pinfunction "7_7") (pintype "passive"))
    )
    (net (code "40") (name "/PB6") (class "Default")
      (node (ref "IC3") (pin "25") (pinfunction "(OC1B/PCINT6)PB6_25") (pintype "passive"))
      (node (ref "JP1") (pin "6") (pinfunction "6_6") (pintype "passive"))
    )
    (net (code "41") (name "/PB7") (class "Default")
      (node (ref "IC3") (pin "26") (pinfunction "(OC0A/OC1C/PCINT7)PB7_26") (pintype "passive"))
      (node (ref "JP1") (pin "5") (pinfunction "5_5") (pintype "passive"))
    )
    (net (code "42") (name "/PC0") (class "Default")
      (node (ref "IC3") (pin "53") (pinfunction "(A8)PC0_53") (pintype "passive"))
      (node (ref "XIO") (pin "18") (pinfunction "18_18") (pintype "passive"))
    )
    (net (code "43") (name "/PC1") (class "Default")
      (node (ref "IC3") (pin "54") (pinfunction "(A9)PC1_54") (pintype "passive"))
      (node (ref "XIO") (pin "17") (pinfunction "17_17") (pintype "passive"))
    )
    (net (code "44") (name "/PC2") (class "Default")
      (node (ref "IC3") (pin "55") (pinfunction "(A10)PC2_55") (pintype "passive"))
      (node (ref "XIO") (pin "16") (pinfunction "16_16") (pintype "passive"))
    )
    (net (code "45") (name "/PC3") (class "Default")
      (node (ref "IC3") (pin "56") (pinfunction "(A11)PC3_56") (pintype "passive"))
      (node (ref "XIO") (pin "15") (pinfunction "15_15") (pintype "passive"))
    )
    (net (code "46") (name "/PC4") (class "Default")
      (node (ref "IC3") (pin "57") (pinfunction "(A12)PC4_57") (pintype "passive"))
      (node (ref "XIO") (pin "14") (pinfunction "14_14") (pintype "passive"))
    )
    (net (code "47") (name "/PC5") (class "Default")
      (node (ref "IC3") (pin "58") (pinfunction "(A13)PC5_58") (pintype "passive"))
      (node (ref "XIO") (pin "13") (pinfunction "13_13") (pintype "passive"))
    )
    (net (code "48") (name "/PC6") (class "Default")
      (node (ref "IC3") (pin "59") (pinfunction "(A14)PC6_59") (pintype "passive"))
      (node (ref "XIO") (pin "12") (pinfunction "12_12") (pintype "passive"))
    )
    (net (code "49") (name "/PC7") (class "Default")
      (node (ref "IC3") (pin "60") (pinfunction "(A15)PC7_60") (pintype "passive"))
      (node (ref "XIO") (pin "11") (pinfunction "11_11") (pintype "passive"))
    )
    (net (code "50") (name "/PD7") (class "Default")
      (node (ref "IC3") (pin "50") (pinfunction "(T0)PD7_50") (pintype "passive"))
      (node (ref "XIO") (pin "19") (pinfunction "19_19") (pintype "passive"))
    )
    (net (code "51") (name "/PE0") (class "Default")
      (node (ref "IC3") (pin "2") (pinfunction "(RXD0/PCIN8)PE0_2") (pintype "passive"))
      (node (ref "PWML") (pin "1") (pinfunction "1_1") (pintype "passive"))
    )
    (net (code "52") (name "/PE1") (class "Default")
      (node (ref "IC3") (pin "3") (pinfunction "(TXD0)PE1_3") (pintype "passive"))
      (node (ref "PWML") (pin "2") (pinfunction "2_2") (pintype "passive"))
    )
    (net (code "53") (name "/PE3") (class "Default")
      (node (ref "IC3") (pin "5") (pinfunction "(OC3A/AIN1)PE3_5") (pintype "passive"))
      (node (ref "PWML") (pin "6") (pinfunction "6_6") (pintype "passive"))
    )
    (net (code "54") (name "/PE4") (class "Default")
      (node (ref "IC3") (pin "6") (pinfunction "(OC3B/INT4)PE4_6") (pintype "passive"))
      (node (ref "PWML") (pin "3") (pinfunction "3_3") (pintype "passive"))
    )
    (net (code "55") (name "/PE5") (class "Default")
      (node (ref "IC3") (pin "7") (pinfunction "(OC3C/INT5)PE5_7") (pintype "passive"))
      (node (ref "PWML") (pin "4") (pinfunction "4_4") (pintype "passive"))
    )
    (net (code "56") (name "/PE6") (class "Default")
      (node (ref "IC3") (pin "8") (pinfunction "(T3/INT6)PE6_8") (pintype "passive"))
      (node (ref "SJ3") (pin "3") (pinfunction "2_3") (pintype "passive"))
    )
    (net (code "57") (name "/PG0") (class "Default")
      (node (ref "IC3") (pin "51") (pinfunction "(WR)PG0_51") (pintype "passive"))
      (node (ref "XIO") (pin "22") (pinfunction "22_22") (pintype "passive"))
    )
    (net (code "58") (name "/PG1") (class "Default")
      (node (ref "IC3") (pin "52") (pinfunction "(RD)PG1_52") (pintype "passive"))
      (node (ref "XIO") (pin "21") (pinfunction "21_21") (pintype "passive"))
    )
    (net (code "59") (name "/PG2") (class "Default")
      (node (ref "IC3") (pin "70") (pinfunction "(ALE)PG2_70") (pintype "passive"))
      (node (ref "XIO") (pin "20") (pinfunction "20_20") (pintype "passive"))
    )
    (net (code "60") (name "/PG5") (class "Default")
      (node (ref "IC3") (pin "1") (pinfunction "(OC0B)PG5_1") (pintype "passive"))
      (node (ref "PWML") (pin "5") (pinfunction "5_5") (pintype "passive"))
    )
    (net (code "61") (name "/PH3") (class "Default")
      (node (ref "IC3") (pin "15") (pinfunction "PH3(OC4A)_15") (pintype "passive"))
      (node (ref "PWML") (pin "7") (pinfunction "7_7") (pintype "passive"))
    )
    (net (code "62") (name "/PH4") (class "Default")
      (node (ref "IC3") (pin "16") (pinfunction "PH4(OC4B)_16") (pintype "passive"))
      (node (ref "PWML") (pin "8") (pinfunction "8_8") (pintype "passive"))
      (node (ref "SJ1") (pin "1") (pinfunction "1_1") (pintype "passive"))
    )
    (net (code "63") (name "/PH5") (class "Default")
      (node (ref "IC3") (pin "17") (pinfunction "PH5(OC4C)_17") (pintype "passive"))
      (node (ref "JP1") (pin "10") (pinfunction "10_10") (pintype "passive"))
    )
    (net (code "64") (name "/PH6") (class "Default")
      (node (ref "IC3") (pin "18") (pinfunction "PH6(OC2B)_18") (pintype "passive"))
      (node (ref "JP1") (pin "9") (pinfunction "9_9") (pintype "passive"))
    )
    (net (code "65") (name "/PH7") (class "Default")
      (node (ref "IC3") (pin "27") (pinfunction "PH7(T4)_27") (pintype "passive"))
      (node (ref "SJ2") (pin "1") (pinfunction "1_1") (pintype "passive"))
    )
    (net (code "66") (name "/PJ2") (class "Default")
      (node (ref "IC3") (pin "65") (pinfunction "PJ2(XCK3/PCINT11)_65") (pintype "passive"))
      (node (ref "SJ1") (pin "3") (pinfunction "2_3") (pintype "passive"))
    )
    (net (code "67") (name "/PJ6") (class "Default")
      (node (ref "IC3") (pin "69") (pinfunction "PJ6(PCINT15)_69") (pintype "passive"))
      (node (ref "SJ3") (pin "1") (pinfunction "1_1") (pintype "passive"))
    )
    (net (code "68") (name "/PL0") (class "Default")
      (node (ref "IC3") (pin "35") (pinfunction "PL0(ICP4)_35") (pintype "passive"))
      (node (ref "XIO") (pin "30") (pinfunction "30_30") (pintype "passive"))
    )
    (net (code "69") (name "/PL1") (class "Default")
      (node (ref "IC3") (pin "36") (pinfunction "PL1(ICP5)_36") (pintype "passive"))
      (node (ref "XIO") (pin "29") (pinfunction "29_29") (pintype "passive"))
    )
    (net (code "70") (name "/PL2") (class "Default")
      (node (ref "IC3") (pin "37") (pinfunction "PL2(T5)_37") (pintype "passive"))
      (node (ref "XIO") (pin "28") (pinfunction "28_28") (pintype "passive"))
    )
    (net (code "71") (name "/PL3") (class "Default")
      (node (ref "IC3") (pin "38") (pinfunction "PL3(OC5A)_38") (pintype "passive"))
      (node (ref "XIO") (pin "27") (pinfunction "27_27") (pintype "passive"))
    )
    (net (code "72") (name "/PL4") (class "Default")
      (node (ref "IC3") (pin "39") (pinfunction "PL4(OC5B)_39") (pintype "passive"))
      (node (ref "XIO") (pin "26") (pinfunction "26_26") (pintype "passive"))
    )
    (net (code "73") (name "/PL5") (class "Default")
      (node (ref "IC3") (pin "40") (pinfunction "PL5(OC5C)_40") (pintype "passive"))
      (node (ref "XIO") (pin "25") (pinfunction "25_25") (pintype "passive"))
    )
    (net (code "74") (name "/PL6") (class "Default")
      (node (ref "IC3") (pin "41") (pinfunction "PL6_41") (pintype "passive"))
      (node (ref "XIO") (pin "24") (pinfunction "24_24") (pintype "passive"))
    )
    (net (code "75") (name "/PL7") (class "Default")
      (node (ref "IC3") (pin "42") (pinfunction "PL7_42") (pintype "passive"))
      (node (ref "XIO") (pin "23") (pinfunction "23_23") (pintype "passive"))
    )
    (net (code "76") (name "/RESET") (class "Default")
      (node (ref "IC3") (pin "30") (pinfunction "RESET_30") (pintype "passive"))
      (node (ref "ICSP") (pin "5") (pinfunction "5_5") (pintype "passive"))
    )
    (net (code "77") (name "/RST_3V3") (class "Default")
      (node (ref "IC5") (pin "4") (pinfunction "Y_4") (pintype "output"))
      (node (ref "U7A") (pin "12") (pinfunction "RES_12") (pintype "passive"))
    )
    (net (code "78") (name "/RST_5V") (class "Default")
      (node (ref "IC5") (pin "2") (pinfunction "A_2") (pintype "input"))
      (node (ref "RN6") (pin "1") (pinfunction "1_1") (pintype "passive"))
      (node (ref "SJ1") (pin "2") (pinfunction "C_2") (pintype "passive"))
    )
    (net (code "79") (name "/RST_BTN") (class "Default")
      (node (ref "C43") (pin "1") (pinfunction "1_1") (pintype "passive"))
      (node (ref "D7") (pin "A") (pinfunction "A_A") (pintype "passive"))
      (node (ref "POWER") (pin "3") (pinfunction "3_3") (pintype "passive"))
      (node (ref "RESET") (pin "3") (pinfunction "3_3") (pintype "passive"))
      (node (ref "RESET") (pin "4") (pinfunction "4_4") (pintype "passive"))
      (node (ref "RN1") (pin "6") (pinfunction "6_6") (pintype "passive"))
    )
    (net (code "80") (name "/RXD1") (class "Default")
      (node (ref "COMMUNICATION") (pin "3") (pinfunction "3_3") (pintype "passive"))
      (node (ref "IC3") (pin "45") (pinfunction "(RXD1/INT2)PD2_45") (pintype "passive"))
    )
    (net (code "81") (name "/RXD2") (class "Default")
      (node (ref "COMMUNICATION") (pin "5") (pinfunction "5_5") (pintype "passive"))
      (node (ref "IC3") (pin "12") (pinfunction "PH0(RXD2)_12") (pintype "passive"))
    )
    (net (code "82") (name "/RXD3") (class "Default")
      (node (ref "COMMUNICATION") (pin "7") (pinfunction "7_7") (pintype "passive"))
      (node (ref "IC3") (pin "63") (pinfunction "PJ0(RXD3/PCINT9)_63") (pintype "passive"))
    )
    (net (code "83") (name "/SCK_3V3") (class "Default")
      (node (ref "IC6") (pin "4") (pinfunction "Y_4") (pintype "output"))
      (node (ref "U7A") (pin "13") (pinfunction "SCK_13") (pintype "passive"))
    )
    (net (code "84") (name "/SCL") (class "Default")
      (node (ref "COMMUNICATION") (pin "1") (pinfunction "1_1") (pintype "passive"))
      (node (ref "IC3") (pin "43") (pinfunction "(SCL/INT0)PD0_43") (pintype "passive"))
      (node (ref "JP1") (pin "1") (pinfunction "1_1") (pintype "passive"))
      (node (ref "RN1") (pin "2") (pinfunction "2_2") (pintype "passive"))
    )
    (net (code "85") (name "/SDA") (class "Default")
      (node (ref "COMMUNICATION") (pin "2") (pinfunction "2_2") (pintype "passive"))
      (node (ref "IC3") (pin "44") (pinfunction "(SDA/INT1)PD1_44") (pintype "passive"))
      (node (ref "JP1") (pin "2") (pinfunction "2_2") (pintype "passive"))
      (node (ref "RN1") (pin "4") (pinfunction "4_4") (pintype "passive"))
    )
    (net (code "86") (name "/SP1_PWR") (class "Default")
      (node (ref "D2") (pin "1") (pinfunction "A1_1") (pintype "passive"))
    )
    (net (code "87") (name "/SP2_PWR") (class "Default")
      (node (ref "D2") (pin "2") (pinfunction "A2_2") (pintype "passive"))
    )
    (net (code "88") (name "/SP3_PWR") (class "Default")
      (node (ref "D5") (pin "1") (pinfunction "A1_1") (pintype "passive"))
    )
    (net (code "89") (name "/SP4_PWR") (class "Default")
      (node (ref "D5") (pin "2") (pinfunction "A2_2") (pintype "passive"))
    )
    (net (code "90") (name "/SP5_PWR") (class "Default")
      (node (ref "D6") (pin "1") (pinfunction "A1_1") (pintype "passive"))
    )
    (net (code "91") (name "/SP6_PWR") (class "Default")
      (node (ref "D6") (pin "2") (pinfunction "A2_2") (pintype "passive"))
    )
    (net (code "92") (name "/SS_3V3") (class "Default")
      (node (ref "IC8") (pin "4") (pinfunction "Y_4") (pintype "output"))
      (node (ref "U7A") (pin "14") (pinfunction "SS_14") (pintype "passive"))
    )
    (net (code "93") (name "/SS_MAX5") (class "Default")
      (node (ref "IC8") (pin "2") (pinfunction "A_2") (pintype "input"))
      (node (ref "RN6") (pin "8") (pinfunction "8_8") (pintype "passive"))
      (node (ref "SJ2") (pin "2") (pinfunction "C_2") (pintype "passive"))
    )
    (net (code "94") (name "/TXD1") (class "Default")
      (node (ref "COMMUNICATION") (pin "4") (pinfunction "4_4") (pintype "passive"))
      (node (ref "IC3") (pin "46") (pinfunction "(TXD1/INT3)PD3_46") (pintype "passive"))
    )
    (net (code "95") (name "/TXD2") (class "Default")
      (node (ref "COMMUNICATION") (pin "6") (pinfunction "6_6") (pintype "passive"))
      (node (ref "IC3") (pin "13") (pinfunction "PH1(TXD2)_13") (pintype "passive"))
    )
    (net (code "96") (name "/TXD3") (class "Default")
      (node (ref "COMMUNICATION") (pin "8") (pinfunction "8_8") (pintype "passive"))
      (node (ref "IC3") (pin "64") (pinfunction "PJ1(TXD3/PCINT10)_64") (pintype "passive"))
    )
    (net (code "97") (name "/VIN") (class "Default")
      (node (ref "POWER") (pin "8") (pinfunction "8_8") (pintype "passive"))
    )
    (net (code "98") (name "/Vdc") (class "Default")
      (node (ref "D1") (pin "2") (pinfunction "K_2") (pintype "passive"))
      (node (ref "D3") (pin "2") (pinfunction "K_2") (pintype "passive"))
      (node (ref "D4") (pin "2") (pinfunction "K_2") (pintype "passive"))
    )
    (net (code "99") (name "/Vin_1") (class "Default")
      (node (ref "C1") (pin "2") (pinfunction "2_2") (pintype "passive"))
      (node (ref "C2") (pin "2") (pinfunction "2_2") (pintype "passive"))
      (node (ref "C3") (pin "2") (pinfunction "2_2") (pintype "passive"))
      (node (ref "D2") (pin "3") (pinfunction "K_3") (pintype "passive"))
      (node (ref "P1") (pin "2") (pinfunction "2_2") (pintype "passive"))
      (node (ref "R1") (pin "2") (pinfunction "2_2") (pintype "passive"))
      (node (ref "U1") (pin "16") (pinfunction "Vin_16") (pintype "power_in"))
    )
    (net (code "100") (name "/Vin_2") (class "Default")
      (node (ref "C11") (pin "2") (pinfunction "2_2") (pintype "passive"))
      (node (ref "C12") (pin "2") (pinfunction "2_2") (pintype "passive"))
      (node (ref "C13") (pin "2") (pinfunction "2_2") (pintype "passive"))
      (node (ref "D5") (pin "3") (pinfunction "K_3") (pintype "passive"))
      (node (ref "P2") (pin "2") (pinfunction "2_2") (pintype "passive"))
      (node (ref "R5") (pin "2") (pinfunction "2_2") (pintype "passive"))
      (node (ref "U2") (pin "16") (pinfunction "Vin_16") (pintype "power_in"))
    )
    (net (code "101") (name "/Vin_3") (class "Default")
      (node (ref "C21") (pin "2") (pinfunction "2_2") (pintype "passive"))
      (node (ref "C22") (pin "2") (pinfunction "2_2") (pintype "passive"))
      (node (ref "C23") (pin "2") (pinfunction "2_2") (pintype "passive"))
      (node (ref "D6") (pin "3") (pinfunction "K_3") (pintype "passive"))
      (node (ref "P3") (pin "2") (pinfunction "2_2") (pintype "passive"))
      (node (ref "R9") (pin "2") (pinfunction "2_2") (pintype "passive"))
      (node (ref "U3") (pin "16") (pinfunction "Vin_16") (pintype "power_in"))
    )
    (net (code "102") (name "/Vout_1") (class "Default")
      (node (ref "C10") (pin "2") (pinfunction "2_2") (pintype "passive"))
      (node (ref "C7") (pin "2") (pinfunction "2_2") (pintype "passive"))
      (node (ref "C8") (pin "2") (pinfunction "2_2") (pintype "passive"))
      (node (ref "C9") (pin "2") (pinfunction "2_2") (pintype "passive"))
      (node (ref "D1") (pin "1") (pinfunction "A_1") (pintype "passive"))
      (node (ref "R4") (pin "2") (pinfunction "2_2") (pintype "passive"))
      (node (ref "U1") (pin "10") (pinfunction "Vout_10") (pintype "power_in"))
    )
    (net (code "103") (name "/Vout_2") (class "Default")
      (node (ref "C17") (pin "2") (pinfunction "2_2") (pintype "passive"))
      (node (ref "C18") (pin "2") (pinfunction "2_2") (pintype "passive"))
      (node (ref "C19") (pin "2") (pinfunction "2_2") (pintype "passive"))
      (node (ref "C20") (pin "2") (pinfunction "2_2") (pintype "passive"))
      (node (ref "D3") (pin "1") (pinfunction "A_1") (pintype "passive"))
      (node (ref "R8") (pin "2") (pinfunction "2_2") (pintype "passive"))
      (node (ref "U2") (pin "10") (pinfunction "Vout_10") (pintype "power_in"))
    )
    (net (code "104") (name "/Vout_3") (class "Default")
      (node (ref "C27") (pin "1") (pinfunction "1_1") (pintype "passive"))
      (node (ref "C28") (pin "2") (pinfunction "2_2") (pintype "passive"))
      (node (ref "C29") (pin "2") (pinfunction "2_2") (pintype "passive"))
      (node (ref "C30") (pin "2") (pinfunction "2_2") (pintype "passive"))
      (node (ref "D4") (pin "1") (pinfunction "A_1") (pintype "passive"))
      (node (ref "R11") (pin "2") (pinfunction "2_2") (pintype "passive"))
      (node (ref "U3") (pin "10") (pinfunction "Vout_10") (pintype "power_in"))
    )
    (net (code "105") (name "/XTAL1") (class "Default")
      (node (ref "IC3") (pin "34") (pinfunction "XTAL1_34") (pintype "passive"))
      (node (ref "Y1") (pin "3") (pinfunction "3_3") (pintype "passive"))
    )
    (net (code "106") (name "/XTAL2") (class "Default")
      (node (ref "IC3") (pin "33") (pinfunction "XTAL2_33") (pintype "output"))
      (node (ref "Y1") (pin "1") (pinfunction "1_1") (pintype "passive"))
    )
    (net (code "107") (name "GND") (class "Default")
      (node (ref "C1") (pin "1") (pinfunction "1_1") (pintype "passive"))
      (node (ref "C10") (pin "1") (pinfunction "1_1") (pintype "passive"))
      (node (ref "C11") (pin "1") (pinfunction "1_1") (pintype "passive"))
      (node (ref "C12") (pin "1") (pinfunction "1_1") (pintype "passive"))
      (node (ref "C13") (pin "1") (pinfunction "1_1") (pintype "passive"))
      (node (ref "C16") (pin "1") (pinfunction "1_1") (pintype "passive"))
      (node (ref "C18") (pin "1") (pinfunction "1_1") (pintype "passive"))
      (node (ref "C19") (pin "1") (pinfunction "1_1") (pintype "passive"))
      (node (ref "C2") (pin "1") (pinfunction "1_1") (pintype "passive"))
      (node (ref "C20") (pin "1") (pinfunction "1_1") (pintype "passive"))
      (node (ref "C21") (pin "1") (pinfunction "1_1") (pintype "passive"))
      (node (ref "C22") (pin "1") (pinfunction "1_1") (pintype "passive"))
      (node (ref "C23") (pin "1") (pinfunction "1_1") (pintype "passive"))
      (node (ref "C26") (pin "1") (pinfunction "1_1") (pintype "passive"))
      (node (ref "C28") (pin "1") (pinfunction "1_1") (pintype "passive"))
      (node (ref "C29") (pin "1") (pinfunction "1_1") (pintype "passive"))
      (node (ref "C3") (pin "1") (pinfunction "1_1") (pintype "passive"))
      (node (ref "C30") (pin "1") (pinfunction "1_1") (pintype "passive"))
      (node (ref "C31") (pin "1") (pinfunction "1_1") (pintype "passive"))
      (node (ref "C32") (pin "1") (pinfunction "1_1") (pintype "passive"))
      (node (ref "C33") (pin "1") (pinfunction "1_1") (pintype "passive"))
      (node (ref "C34") (pin "1") (pinfunction "1_1") (pintype "passive"))
      (node (ref "C37") (pin "1") (pinfunction "1_1") (pintype "passive"))
      (node (ref "C38") (pin "1") (pinfunction "1_1") (pintype "passive"))
      (node (ref "C42") (pin "1") (pinfunction "1_1") (pintype "passive"))
      (node (ref "C43") (pin "2") (pinfunction "2_2") (pintype "passive"))
      (node (ref "C44") (pin "2") (pinfunction "2_2") (pintype "passive"))
      (node (ref "C45") (pin "2") (pinfunction "2_2") (pintype "passive"))
      (node (ref "C46") (pin "2") (pinfunction "2_2") (pintype "passive"))
      (node (ref "C47") (pin "2") (pinfunction "2_2") (pintype "passive"))
      (node (ref "C48") (pin "2") (pinfunction "2_2") (pintype "passive"))
      (node (ref "C49") (pin "2") (pinfunction "2_2") (pintype "passive"))
      (node (ref "C50") (pin "2") (pinfunction "2_2") (pintype "passive"))
      (node (ref "C51") (pin "2") (pinfunction "2_2") (pintype "passive"))
      (node (ref "C52") (pin "1") (pinfunction "1_1") (pintype "passive"))
      (node (ref "C53") (pin "1") (pinfunction "1_1") (pintype "passive"))
      (node (ref "C54") (pin "2") (pinfunction "2_2") (pintype "passive"))
      (node (ref "C6") (pin "1") (pinfunction "1_1") (pintype "passive"))
      (node (ref "C8") (pin "1") (pinfunction "1_1") (pintype "passive"))
      (node (ref "C9") (pin "1") (pinfunction "1_1") (pintype "passive"))
      (node (ref "IC3") (pin "11") (pinfunction "GND_11") (pintype "power_in"))
      (node (ref "IC3") (pin "32") (pinfunction "GND1_32") (pintype "power_in"))
      (node (ref "IC3") (pin "62") (pinfunction "GND2_62") (pintype "power_in"))
      (node (ref "IC3") (pin "81") (pinfunction "GND3_81") (pintype "power_in"))
      (node (ref "IC3") (pin "99") (pinfunction "AGND_99") (pintype "power_in"))
      (node (ref "IC5") (pin "1") (pinfunction "~{OE}_1") (pintype "input"))
      (node (ref "IC5") (pin "3") (pinfunction "GND_3") (pintype "passive"))
      (node (ref "IC6") (pin "1") (pinfunction "~{OE}_1") (pintype "input"))
      (node (ref "IC6") (pin "3") (pinfunction "GND_3") (pintype "passive"))
      (node (ref "IC8") (pin "1") (pinfunction "~{OE}_1") (pintype "input"))
      (node (ref "IC8") (pin "3") (pinfunction "GND_3") (pintype "passive"))
      (node (ref "IC9") (pin "1") (pinfunction "~{OE}_1") (pintype "input"))
      (node (ref "IC9") (pin "3") (pinfunction "GND_3") (pintype "passive"))
      (node (ref "ICSP") (pin "6") (pinfunction "6_6") (pintype "passive"))
      (node (ref "JP1") (pin "4") (pinfunction "4_4") (pintype "passive"))
      (node (ref "POWER") (pin "6") (pinfunction "6_6") (pintype "passive"))
      (node (ref "POWER") (pin "7") (pinfunction "7_7") (pintype "passive"))
      (node (ref "R10") (pin "1") (pinfunction "1_1") (pintype "passive"))
      (node (ref "R12") (pin "1") (pinfunction "1_1") (pintype "passive"))
      (node (ref "R13") (pin "1") (pinfunction "1_1") (pintype "passive"))
      (node (ref "R17") (pin "1") (pinfunction "1_1") (pintype "passive"))
      (node (ref "R2") (pin "1") (pinfunction "1_1") (pintype "passive"))
      (node (ref "R3") (pin "1") (pinfunction "1_1") (pintype "passive"))
      (node (ref "R6") (pin "1") (pinfunction "1_1") (pintype "passive"))
      (node (ref "R7") (pin "1") (pinfunction "1_1") (pintype "passive"))
      (node (ref "RESET") (pin "1") (pinfunction "1_1") (pintype "passive"))
      (node (ref "RESET") (pin "2") (pinfunction "2_2") (pintype "passive"))
      (node (ref "RN6") (pin "2") (pinfunction "2_2") (pintype "passive"))
      (node (ref "U1") (pin "13") (pinfunction "PGND_13") (pintype "power_in"))
      (node (ref "U1") (pin "17") (pinfunction "PGND_17") (pintype "power_in"))
      (node (ref "U1") (pin "4") (pinfunction "GND_4") (pintype "power_in"))
      (node (ref "U1") (pin "6") (pinfunction "NC_6") (pintype "passive"))
      (node (ref "U1") (pin "7") (pinfunction "NC_7") (pintype "passive"))
      (node (ref "U1") (pin "9") (pinfunction "PGOOD_9") (pintype "input"))
      (node (ref "U2") (pin "13") (pinfunction "PGND_13") (pintype "power_in"))
      (node (ref "U2") (pin "17") (pinfunction "PGND_17") (pintype "power_in"))
      (node (ref "U2") (pin "4") (pinfunction "GND_4") (pintype "power_in"))
      (node (ref "U2") (pin "6") (pinfunction "NC_6") (pintype "passive"))
      (node (ref "U2") (pin "7") (pinfunction "NC_7") (pintype "passive"))
      (node (ref "U2") (pin "9") (pinfunction "PGOOD_9") (pintype "input"))
      (node (ref "U3") (pin "13") (pinfunction "PGND_13") (pintype "power_in"))
      (node (ref "U3") (pin "17") (pinfunction "PGND_17") (pintype "power_in"))
      (node (ref "U3") (pin "4") (pinfunction "GND_4") (pintype "power_in"))
      (node (ref "U3") (pin "6") (pinfunction "NC_6") (pintype "passive"))
      (node (ref "U3") (pin "7") (pinfunction "NC_7") (pintype "passive"))
      (node (ref "U3") (pin "9") (pinfunction "PGOOD_9") (pintype "input"))
      (node (ref "U4") (pin "10") (pinfunction "PGND_10") (pintype "passive"))
      (node (ref "U4") (pin "11") (pinfunction "PGND_11") (pintype "passive"))
      (node (ref "U4") (pin "3") (pinfunction "SGND_3") (pintype "passive"))
      (node (ref "U5") (pin "17") (pinfunction "GND_17") (pintype "passive"))
      (node (ref "U5") (pin "3") (pinfunction "OVP_3") (pintype "input"))
      (node (ref "U7A") (pin "19") (pinfunction "GND_19") (pintype "passive"))
      (node (ref "U7A") (pin "3") (pinfunction "GND_3") (pintype "passive"))
      (node (ref "X3") (pin "4") (pinfunction "4_4") (pintype "passive"))
      (node (ref "XIO") (pin "35") (pinfunction "35_35") (pintype "passive"))
      (node (ref "XIO") (pin "36") (pinfunction "36_36") (pintype "passive"))
      (node (ref "Y1") (pin "2") (pinfunction "2_2") (pintype "passive"))
      (node (ref "Y3") (pin "2") (pinfunction "GND_2") (pintype "passive"))
      (node (ref "Y3") (pin "4") (pinfunction "GND_4") (pintype "passive"))
    )
    (net (code "108") (name "Net-(C34-Pad2)") (class "Default")
      (node (ref "C34") (pin "2") (pinfunction "2_2") (pintype "passive"))
      (node (ref "P5") (pin "2") (pinfunction "2_2") (pintype "passive"))
      (node (ref "P6") (pin "1") (pinfunction "1_1") (pintype "passive"))
      (node (ref "U5") (pin "4") (pinfunction "V_IN_4") (pintype "passive"))
      (node (ref "U5") (pin "5") (pinfunction "V_IN_5") (pintype "passive"))
    )
    (net (code "109") (name "Net-(C35-Pad1)") (class "Default")
      (node (ref "C35") (pin "1") (pinfunction "1_1") (pintype "passive"))
      (node (ref "L5") (pin "2") (pinfunction "2_2") (pintype "passive"))
      (node (ref "U5") (pin "12") (pinfunction "SW1_12") (pintype "passive"))
      (node (ref "U5") (pin "13") (pinfunction "SW1_13") (pintype "passive"))
    )
    (net (code "110") (name "Net-(C36-Pad1)") (class "Default")
      (node (ref "C36") (pin "1") (pinfunction "1_1") (pintype "passive"))
      (node (ref "L5") (pin "1") (pinfunction "1_1") (pintype "passive"))
      (node (ref "U5") (pin "10") (pinfunction "SW2_10") (pintype "passive"))
      (node (ref "U5") (pin "9") (pinfunction "SW2_9") (pintype "passive"))
    )
    (net (code "111") (name "Net-(C40-Pad2)") (class "Default")
      (node (ref "C40") (pin "2") (pinfunction "2_2") (pintype "passive"))
      (node (ref "R14") (pin "2") (pinfunction "2_2") (pintype "passive"))
    )
    (net (code "112") (name "Net-(C41-Pad2)") (class "Default")
      (node (ref "C41") (pin "2") (pinfunction "2_2") (pintype "passive"))
      (node (ref "R16") (pin "2") (pinfunction "2_2") (pintype "passive"))
    )
    (net (code "113") (name "Net-(C51-Pad1)") (class "Default")
      (node (ref "C51") (pin "1") (pinfunction "1_1") (pintype "passive"))
      (node (ref "F2") (pin "1") (pinfunction "1_1") (pintype "passive"))
      (node (ref "L7") (pin "2") (pinfunction "2_2") (pintype "passive"))
    )
    (net (code "114") (name "Net-(F2-Pad2)") (class "Default")
      (node (ref "F2") (pin "2") (pinfunction "2_2") (pintype "passive"))
      (node (ref "X3") (pin "1") (pinfunction "1_1") (pintype "passive"))
    )
    (net (code "115") (name "Net-(L4-Pad1)") (class "Default")
      (node (ref "L4") (pin "1") (pinfunction "1_1") (pintype "passive"))
      (node (ref "U4") (pin "8") (pinfunction "SW_8") (pintype "passive"))
      (node (ref "U4") (pin "9") (pinfunction "SW_9") (pintype "passive"))
    )
    (net (code "116") (name "Net-(RN7-Pad1)") (class "Default")
      (node (ref "RN7") (pin "1") (pinfunction "1_1") (pintype "passive"))
      (node (ref "X3") (pin "2") (pinfunction "2_2") (pintype "passive"))
      (node (ref "Z4") (pin "2") (pinfunction "2_2") (pintype "passive"))
    )
    (net (code "117") (name "Net-(RN7-Pad3)") (class "Default")
      (node (ref "RN7") (pin "3") (pinfunction "3_3") (pintype "passive"))
      (node (ref "X3") (pin "3") (pinfunction "3_3") (pintype "passive"))
      (node (ref "Z3") (pin "2") (pinfunction "2_2") (pintype "passive"))
    )
    (net (code "118") (name "Net-(U1-BST1)") (class "Default")
      (node (ref "C5") (pin "1") (pinfunction "1_1") (pintype "passive"))
      (node (ref "U1") (pin "15") (pinfunction "BST1_15") (pintype "power_in"))
    )
    (net (code "119") (name "Net-(U1-BST2)") (class "Default")
      (node (ref "C4") (pin "1") (pinfunction "1_1") (pintype "passive"))
      (node (ref "U1") (pin "11") (pinfunction "BST2_11") (pintype "power_in"))
    )
    (net (code "120") (name "Net-(U1-FB)") (class "Default")
      (node (ref "C7") (pin "1") (pinfunction "1_1") (pintype "passive"))
      (node (ref "R3") (pin "2") (pinfunction "2_2") (pintype "passive"))
      (node (ref "R4") (pin "1") (pinfunction "1_1") (pintype "passive"))
      (node (ref "U1") (pin "5") (pinfunction "FB_5") (pintype "input"))
    )
    (net (code "121") (name "Net-(U1-MPPC)") (class "Default")
      (node (ref "R1") (pin "1") (pinfunction "1_1") (pintype "passive"))
      (node (ref "R2") (pin "2") (pinfunction "2_2") (pintype "passive"))
      (node (ref "U1") (pin "3") (pinfunction "MPPC_3") (pintype "input"))
    )
    (net (code "122") (name "Net-(U1-PWM)") (class "Default")
      (node (ref "C6") (pin "2") (pinfunction "2_2") (pintype "passive"))
      (node (ref "U1") (pin "1") (pinfunction "Vcc_1") (pintype "power_in"))
      (node (ref "U1") (pin "8") (pinfunction "PWM_8") (pintype "input"))
    )
    (net (code "123") (name "Net-(U1-RUN)") (class "Default")
      (node (ref "P1") (pin "1") (pinfunction "1_1") (pintype "passive"))
      (node (ref "U1") (pin "2") (pinfunction "RUN_2") (pintype "input"))
    )
    (net (code "124") (name "Net-(U1-SW1)") (class "Default")
      (node (ref "C5") (pin "2") (pinfunction "2_2") (pintype "passive"))
      (node (ref "L1") (pin "1") (pinfunction "1_1") (pintype "passive"))
      (node (ref "U1") (pin "14") (pinfunction "SW1_14") (pintype "power_in"))
    )
    (net (code "125") (name "Net-(U1-SW2)") (class "Default")
      (node (ref "C4") (pin "2") (pinfunction "2_2") (pintype "passive"))
      (node (ref "L1") (pin "2") (pinfunction "2_2") (pintype "passive"))
      (node (ref "U1") (pin "12") (pinfunction "SW2_12") (pintype "power_in"))
    )
    (net (code "126") (name "Net-(U2-BST1)") (class "Default")
      (node (ref "C14") (pin "1") (pinfunction "1_1") (pintype "passive"))
      (node (ref "U2") (pin "15") (pinfunction "BST1_15") (pintype "power_in"))
    )
    (net (code "127") (name "Net-(U2-BST2)") (class "Default")
      (node (ref "C15") (pin "1") (pinfunction "1_1") (pintype "passive"))
      (node (ref "U2") (pin "11") (pinfunction "BST2_11") (pintype "power_in"))
    )
    (net (code "128") (name "Net-(U2-FB)") (class "Default")
      (node (ref "C17") (pin "1") (pinfunction "1_1") (pintype "passive"))
      (node (ref "R7") (pin "2") (pinfunction "2_2") (pintype "passive"))
      (node (ref "R8") (pin "1") (pinfunction "1_1") (pintype "passive"))
      (node (ref "U2") (pin "5") (pinfunction "FB_5") (pintype "input"))
    )
    (net (code "129") (name "Net-(U2-MPPC)") (class "Default")
      (node (ref "R5") (pin "1") (pinfunction "1_1") (pintype "passive"))
      (node (ref "R6") (pin "2") (pinfunction "2_2") (pintype "passive"))
      (node (ref "U2") (pin "3") (pinfunction "MPPC_3") (pintype "input"))
    )
    (net (code "130") (name "Net-(U2-PWM)") (class "Default")
      (node (ref "C16") (pin "2") (pinfunction "2_2") (pintype "passive"))
      (node (ref "U2") (pin "1") (pinfunction "Vcc_1") (pintype "power_in"))
      (node (ref "U2") (pin "8") (pinfunction "PWM_8") (pintype "input"))
    )
    (net (code "131") (name "Net-(U2-RUN)") (class "Default")
      (node (ref "P2") (pin "1") (pinfunction "1_1") (pintype "passive"))
      (node (ref "U2") (pin "2") (pinfunction "RUN_2") (pintype "input"))
    )
    (net (code "132") (name "Net-(U2-SW1)") (class "Default")
      (node (ref "C14") (pin "2") (pinfunction "2_2") (pintype "passive"))
      (node (ref "L2") (pin "1") (pinfunction "1_1") (pintype "passive"))
      (node (ref "U2") (pin "14") (pinfunction "SW1_14") (pintype "power_in"))
    )
    (net (code "133") (name "Net-(U2-SW2)") (class "Default")
      (node (ref "C15") (pin "2") (pinfunction "2_2") (pintype "passive"))
      (node (ref "L2") (pin "2") (pinfunction "2_2") (pintype "passive"))
      (node (ref "U2") (pin "12") (pinfunction "SW2_12") (pintype "power_in"))
    )
    (net (code "134") (name "Net-(U3-BST1)") (class "Default")
      (node (ref "C24") (pin "1") (pinfunction "1_1") (pintype "passive"))
      (node (ref "U3") (pin "15") (pinfunction "BST1_15") (pintype "power_in"))
    )
    (net (code "135") (name "Net-(U3-BST2)") (class "Default")
      (node (ref "C25") (pin "1") (pinfunction "1_1") (pintype "passive"))
      (node (ref "U3") (pin "11") (pinfunction "BST2_11") (pintype "power_in"))
    )
    (net (code "136") (name "Net-(U3-FB)") (class "Default")
      (node (ref "C27") (pin "2") (pinfunction "2_2") (pintype "passive"))
      (node (ref "R11") (pin "1") (pinfunction "1_1") (pintype "passive"))
      (node (ref "R12") (pin "2") (pinfunction "2_2") (pintype "passive"))
      (node (ref "U3") (pin "5") (pinfunction "FB_5") (pintype "input"))
    )
    (net (code "137") (name "Net-(U3-MPPC)") (class "Default")
      (node (ref "R10") (pin "2") (pinfunction "2_2") (pintype "passive"))
      (node (ref "R9") (pin "1") (pinfunction "1_1") (pintype "passive"))
      (node (ref "U3") (pin "3") (pinfunction "MPPC_3") (pintype "input"))
    )
    (net (code "138") (name "Net-(U3-PWM)") (class "Default")
      (node (ref "C26") (pin "2") (pinfunction "2_2") (pintype "passive"))
      (node (ref "U3") (pin "1") (pinfunction "Vcc_1") (pintype "power_in"))
      (node (ref "U3") (pin "8") (pinfunction "PWM_8") (pintype "input"))
    )
    (net (code "139") (name "Net-(U3-RUN)") (class "Default")
      (node (ref "P3") (pin "1") (pinfunction "1_1") (pintype "passive"))
      (node (ref "U3") (pin "2") (pinfunction "RUN_2") (pintype "input"))
    )
    (net (code "140") (name "Net-(U3-SW1)") (class "Default")
      (node (ref "C24") (pin "2") (pinfunction "2_2") (pintype "passive"))
      (node (ref "L3") (pin "1") (pinfunction "1_1") (pintype "passive"))
      (node (ref "U3") (pin "14") (pinfunction "SW1_14") (pintype "power_in"))
    )
    (net (code "141") (name "Net-(U3-SW2)") (class "Default")
      (node (ref "C25") (pin "2") (pinfunction "2_2") (pintype "passive"))
      (node (ref "L3") (pin "2") (pinfunction "2_2") (pintype "passive"))
      (node (ref "U3") (pin "12") (pinfunction "SW2_12") (pintype "power_in"))
    )
    (net (code "142") (name "Net-(U4-EN)") (class "Default")
      (node (ref "P4") (pin "1") (pinfunction "1_1") (pintype "passive"))
      (node (ref "U4") (pin "2") (pinfunction "EN_2") (pintype "passive"))
    )
    (net (code "143") (name "Net-(U4-SS)") (class "Default")
      (node (ref "C32") (pin "2") (pinfunction "2_2") (pintype "passive"))
      (node (ref "U4") (pin "4") (pinfunction "SS_4") (pintype "passive"))
    )
    (net (code "144") (name "Net-(U5-BST1)") (class "Default")
      (node (ref "C35") (pin "2") (pinfunction "2_2") (pintype "passive"))
      (node (ref "U5") (pin "14") (pinfunction "BST1_14") (pintype "passive"))
    )
    (net (code "145") (name "Net-(U5-BST2)") (class "Default")
      (node (ref "C36") (pin "2") (pinfunction "2_2") (pintype "passive"))
      (node (ref "U5") (pin "11") (pinfunction "BST2_11") (pintype "passive"))
    )
    (net (code "146") (name "Net-(U5-COMP)") (class "Default")
      (node (ref "C39") (pin "2") (pinfunction "2_2") (pintype "passive"))
      (node (ref "C40") (pin "1") (pinfunction "1_1") (pintype "passive"))
      (node (ref "U5") (pin "1") (pinfunction "COMP_1") (pintype "passive"))
    )
    (net (code "147") (name "Net-(U5-FB)") (class "Default")
      (node (ref "C39") (pin "1") (pinfunction "1_1") (pintype "passive"))
      (node (ref "R14") (pin "1") (pinfunction "1_1") (pintype "passive"))
      (node (ref "R15") (pin "1") (pinfunction "1_1") (pintype "passive"))
      (node (ref "R16") (pin "1") (pinfunction "1_1") (pintype "passive"))
      (node (ref "R17") (pin "2") (pinfunction "2_2") (pintype "passive"))
      (node (ref "U5") (pin "2") (pinfunction "FB_2") (pintype "input"))
    )
    (net (code "148") (name "Net-(U5-I_OUT)") (class "Default")
      (node (ref "C38") (pin "2") (pinfunction "2_2") (pintype "passive"))
      (node (ref "R13") (pin "2") (pinfunction "2_2") (pintype "passive"))
      (node (ref "U5") (pin "7") (pinfunction "I_OUT_7") (pintype "output"))
    )
    (net (code "149") (name "Net-(U5-PWM{slash}SYNC)") (class "Default")
      (node (ref "C37") (pin "2") (pinfunction "2_2") (pintype "passive"))
      (node (ref "U5") (pin "15") (pinfunction "VCC_15") (pintype "passive"))
      (node (ref "U5") (pin "16") (pinfunction "PWM/SYNC_16") (pintype "input"))
    )
    (net (code "150") (name "Net-(U5-RUN)") (class "Default")
      (node (ref "P5") (pin "1") (pinfunction "1_1") (pintype "passive"))
      (node (ref "U5") (pin "6") (pinfunction "RUN_6") (pintype "input"))
    )
    (net (code "151") (name "Net-(U7A-D+)") (class "Default")
      (node (ref "RN7") (pin "4") (pinfunction "4_4") (pintype "passive"))
      (node (ref "U7A") (pin "21") (pinfunction "D+_21") (pintype "passive"))
    )
    (net (code "152") (name "Net-(U7A-D-)") (class "Default")
      (node (ref "RN7") (pin "2") (pinfunction "2_2") (pintype "passive"))
      (node (ref "U7A") (pin "20") (pinfunction "D-_20") (pintype "passive"))
    )
    (net (code "153") (name "Net-(U7A-VBCOMP)") (class "Default")
      (node (ref "C54") (pin "1") (pinfunction "1_1") (pintype "passive"))
      (node (ref "U7A") (pin "22") (pinfunction "VBCOMP_22") (pintype "passive"))
    )
    (net (code "154") (name "Net-(U7A-XI)") (class "Default")
      (node (ref "C53") (pin "2") (pinfunction "2_2") (pintype "passive"))
      (node (ref "U7A") (pin "24") (pinfunction "XI_24") (pintype "passive"))
      (node (ref "Y3") (pin "1") (pinfunction "C1_1") (pintype "passive"))
    )
    (net (code "155") (name "Net-(U7A-XO)") (class "Default")
      (node (ref "C52") (pin "2") (pinfunction "2_2") (pintype "passive"))
      (node (ref "U7A") (pin "25") (pinfunction "XO_25") (pintype "passive"))
      (node (ref "Y3") (pin "3") (pinfunction "C2_3") (pintype "passive"))
    )
    (net (code "156") (name "Net-(X3-PadS1)") (class "Default")
      (node (ref "X3") (pin "S1") (pinfunction "S1_S1") (pintype "passive"))
      (node (ref "X3") (pin "S2") (pinfunction "S2_S2") (pintype "passive"))
      (node (ref "Z3") (pin "1") (pinfunction "1_1") (pintype "passive"))
      (node (ref "Z4") (pin "1") (pinfunction "1_1") (pintype "passive"))
    )
    (net (code "157") (name "unconnected-(IC3-(CLKO{slash}ICP3{slash}INT7)PE7-Pad9)") (class "Default")
      (node (ref "IC3") (pin "9") (pinfunction "(CLKO/ICP3/INT7)PE7_9") (pintype "passive"))
    )
    (net (code "158") (name "unconnected-(IC3-(ICP1)PD4-Pad47)") (class "Default")
      (node (ref "IC3") (pin "47") (pinfunction "(ICP1)PD4_47") (pintype "passive"))
    )
    (net (code "159") (name "unconnected-(IC3-(T1)PD6-Pad49)") (class "Default")
      (node (ref "IC3") (pin "49") (pinfunction "(T1)PD6_49") (pintype "passive"))
    )
    (net (code "160") (name "unconnected-(IC3-(TOSC1)PG4-Pad29)") (class "Default")
      (node (ref "IC3") (pin "29") (pinfunction "(TOSC1)PG4_29") (pintype "passive"))
    )
    (net (code "161") (name "unconnected-(IC3-(TOSC2)PG3-Pad28)") (class "Default")
      (node (ref "IC3") (pin "28") (pinfunction "(TOSC2)PG3_28") (pintype "passive"))
    )
    (net (code "162") (name "unconnected-(IC3-(XCK0{slash}AIN0)PE2-Pad4)") (class "Default")
      (node (ref "IC3") (pin "4") (pinfunction "(XCK0/AIN0)PE2_4") (pintype "passive"))
    )
    (net (code "163") (name "unconnected-(IC3-(XCK1)PD5-Pad48)") (class "Default")
      (node (ref "IC3") (pin "48") (pinfunction "(XCK1)PD5_48") (pintype "passive"))
    )
    (net (code "164") (name "unconnected-(IC3-PH2(XCK2)-Pad14)") (class "Default")
      (node (ref "IC3") (pin "14") (pinfunction "PH2(XCK2)_14") (pintype "passive"))
    )
    (net (code "165") (name "unconnected-(IC3-PJ4(PCINT13)-Pad67)") (class "Default")
      (node (ref "IC3") (pin "67") (pinfunction "PJ4(PCINT13)_67") (pintype "passive"))
    )
    (net (code "166") (name "unconnected-(IC3-PJ5(PCINT14)-Pad68)") (class "Default")
      (node (ref "IC3") (pin "68") (pinfunction "PJ5(PCINT14)_68") (pintype "passive"))
    )
    (net (code "167") (name "unconnected-(IC3-PJ7-Pad79)") (class "Default")
      (node (ref "IC3") (pin "79") (pinfunction "PJ7_79") (pintype "passive"))
    )
    (net (code "168") (name "unconnected-(POWER-Pad1)") (class "Default")
      (node (ref "POWER") (pin "1") (pinfunction "1_1") (pintype "passive"))
    )
    (net (code "169") (name "unconnected-(RESET-5-GND-Pad5)") (class "Default")
      (node (ref "RESET") (pin "5") (pinfunction "5-GND_5") (pintype "power_in"))
    )
    (net (code "170") (name "unconnected-(RN1-Pad7)") (class "Default")
      (node (ref "RN1") (pin "7") (pinfunction "7_7") (pintype "passive"))
    )
    (net (code "171") (name "unconnected-(RN1-Pad8)") (class "Default")
      (node (ref "RN1") (pin "8") (pinfunction "8_8") (pintype "passive"))
    )
    (net (code "172") (name "unconnected-(RN6-Pad5)") (class "Default")
      (node (ref "RN6") (pin "5") (pinfunction "5_5") (pintype "passive"))
    )
    (net (code "173") (name "unconnected-(RN6-Pad6)") (class "Default")
      (node (ref "RN6") (pin "6") (pinfunction "6_6") (pintype "passive"))
    )
    (net (code "174") (name "unconnected-(RN7-Pad5)") (class "Default")
      (node (ref "RN7") (pin "5") (pinfunction "5_5") (pintype "passive"))
    )
    (net (code "175") (name "unconnected-(RN7-Pad6)") (class "Default")
      (node (ref "RN7") (pin "6") (pinfunction "6_6") (pintype "passive"))
    )
    (net (code "176") (name "unconnected-(RN7-Pad7)") (class "Default")
      (node (ref "RN7") (pin "7") (pinfunction "7_7") (pintype "passive"))
    )
    (net (code "177") (name "unconnected-(RN7-Pad8)") (class "Default")
      (node (ref "RN7") (pin "8") (pinfunction "8_8") (pintype "passive"))
    )
    (net (code "178") (name "unconnected-(U4-NC-Pad5)") (class "Default")
      (node (ref "U4") (pin "5") (pinfunction "NC_5") (pintype "passive"))
    )
    (net (code "179") (name "unconnected-(U4-NC-Pad12)") (class "Default")
      (node (ref "U4") (pin "12") (pinfunction "NC_12") (pintype "passive"))
    )
    (net (code "180") (name "unconnected-(U4-NC-Pad13)") (class "Default")
      (node (ref "U4") (pin "13") (pinfunction "NC_13") (pintype "passive"))
    )
    (net (code "181") (name "unconnected-(U7A-GPIN0-Pad26)") (class "Default")
      (node (ref "U7A") (pin "26") (pinfunction "GPIN0_26") (pintype "passive"))
    )
    (net (code "182") (name "unconnected-(U7A-GPIN1-Pad27)") (class "Default")
      (node (ref "U7A") (pin "27") (pinfunction "GPIN1_27") (pintype "passive"))
    )
    (net (code "183") (name "unconnected-(U7A-GPIN2-Pad28)") (class "Default")
      (node (ref "U7A") (pin "28") (pinfunction "GPIN2_28") (pintype "passive"))
    )
    (net (code "184") (name "unconnected-(U7A-GPIN3-Pad29)") (class "Default")
      (node (ref "U7A") (pin "29") (pinfunction "GPIN3_29") (pintype "passive"))
    )
    (net (code "185") (name "unconnected-(U7A-GPIN4-Pad30)") (class "Default")
      (node (ref "U7A") (pin "30") (pinfunction "GPIN4_30") (pintype "passive"))
    )
    (net (code "186") (name "unconnected-(U7A-GPIN5-Pad31)") (class "Default")
      (node (ref "U7A") (pin "31") (pinfunction "GPIN5_31") (pintype "passive"))
    )
    (net (code "187") (name "unconnected-(U7A-GPIN6-Pad32)") (class "Default")
      (node (ref "U7A") (pin "32") (pinfunction "GPIN6_32") (pintype "passive"))
    )
    (net (code "188") (name "unconnected-(U7A-GPIN7-Pad1)") (class "Default")
      (node (ref "U7A") (pin "1") (pinfunction "GPIN7_1") (pintype "passive"))
    )
    (net (code "189") (name "unconnected-(U7A-GPOUT0-Pad4)") (class "Default")
      (node (ref "U7A") (pin "4") (pinfunction "GPOUT0_4") (pintype "passive"))
    )
    (net (code "190") (name "unconnected-(U7A-GPOUT1-Pad5)") (class "Default")
      (node (ref "U7A") (pin "5") (pinfunction "GPOUT1_5") (pintype "passive"))
    )
    (net (code "191") (name "unconnected-(U7A-GPOUT2-Pad6)") (class "Default")
      (node (ref "U7A") (pin "6") (pinfunction "GPOUT2_6") (pintype "passive"))
    )
    (net (code "192") (name "unconnected-(U7A-GPOUT3-Pad7)") (class "Default")
      (node (ref "U7A") (pin "7") (pinfunction "GPOUT3_7") (pintype "passive"))
    )
    (net (code "193") (name "unconnected-(U7A-GPOUT4-Pad8)") (class "Default")
      (node (ref "U7A") (pin "8") (pinfunction "GPOUT4_8") (pintype "passive"))
    )
    (net (code "194") (name "unconnected-(U7A-GPOUT5-Pad9)") (class "Default")
      (node (ref "U7A") (pin "9") (pinfunction "GPOUT5_9") (pintype "passive"))
    )
    (net (code "195") (name "unconnected-(U7A-GPOUT6-Pad10)") (class "Default")
      (node (ref "U7A") (pin "10") (pinfunction "GPOUT6_10") (pintype "passive"))
    )
    (net (code "196") (name "unconnected-(U7A-GPOUT7-Pad11)") (class "Default")
      (node (ref "U7A") (pin "11") (pinfunction "GPOUT7_11") (pintype "passive"))
    )
  )
)
